# PhotonOnAStick-Wide.net
KiCad netlist of a schematic drawn in EAGLE
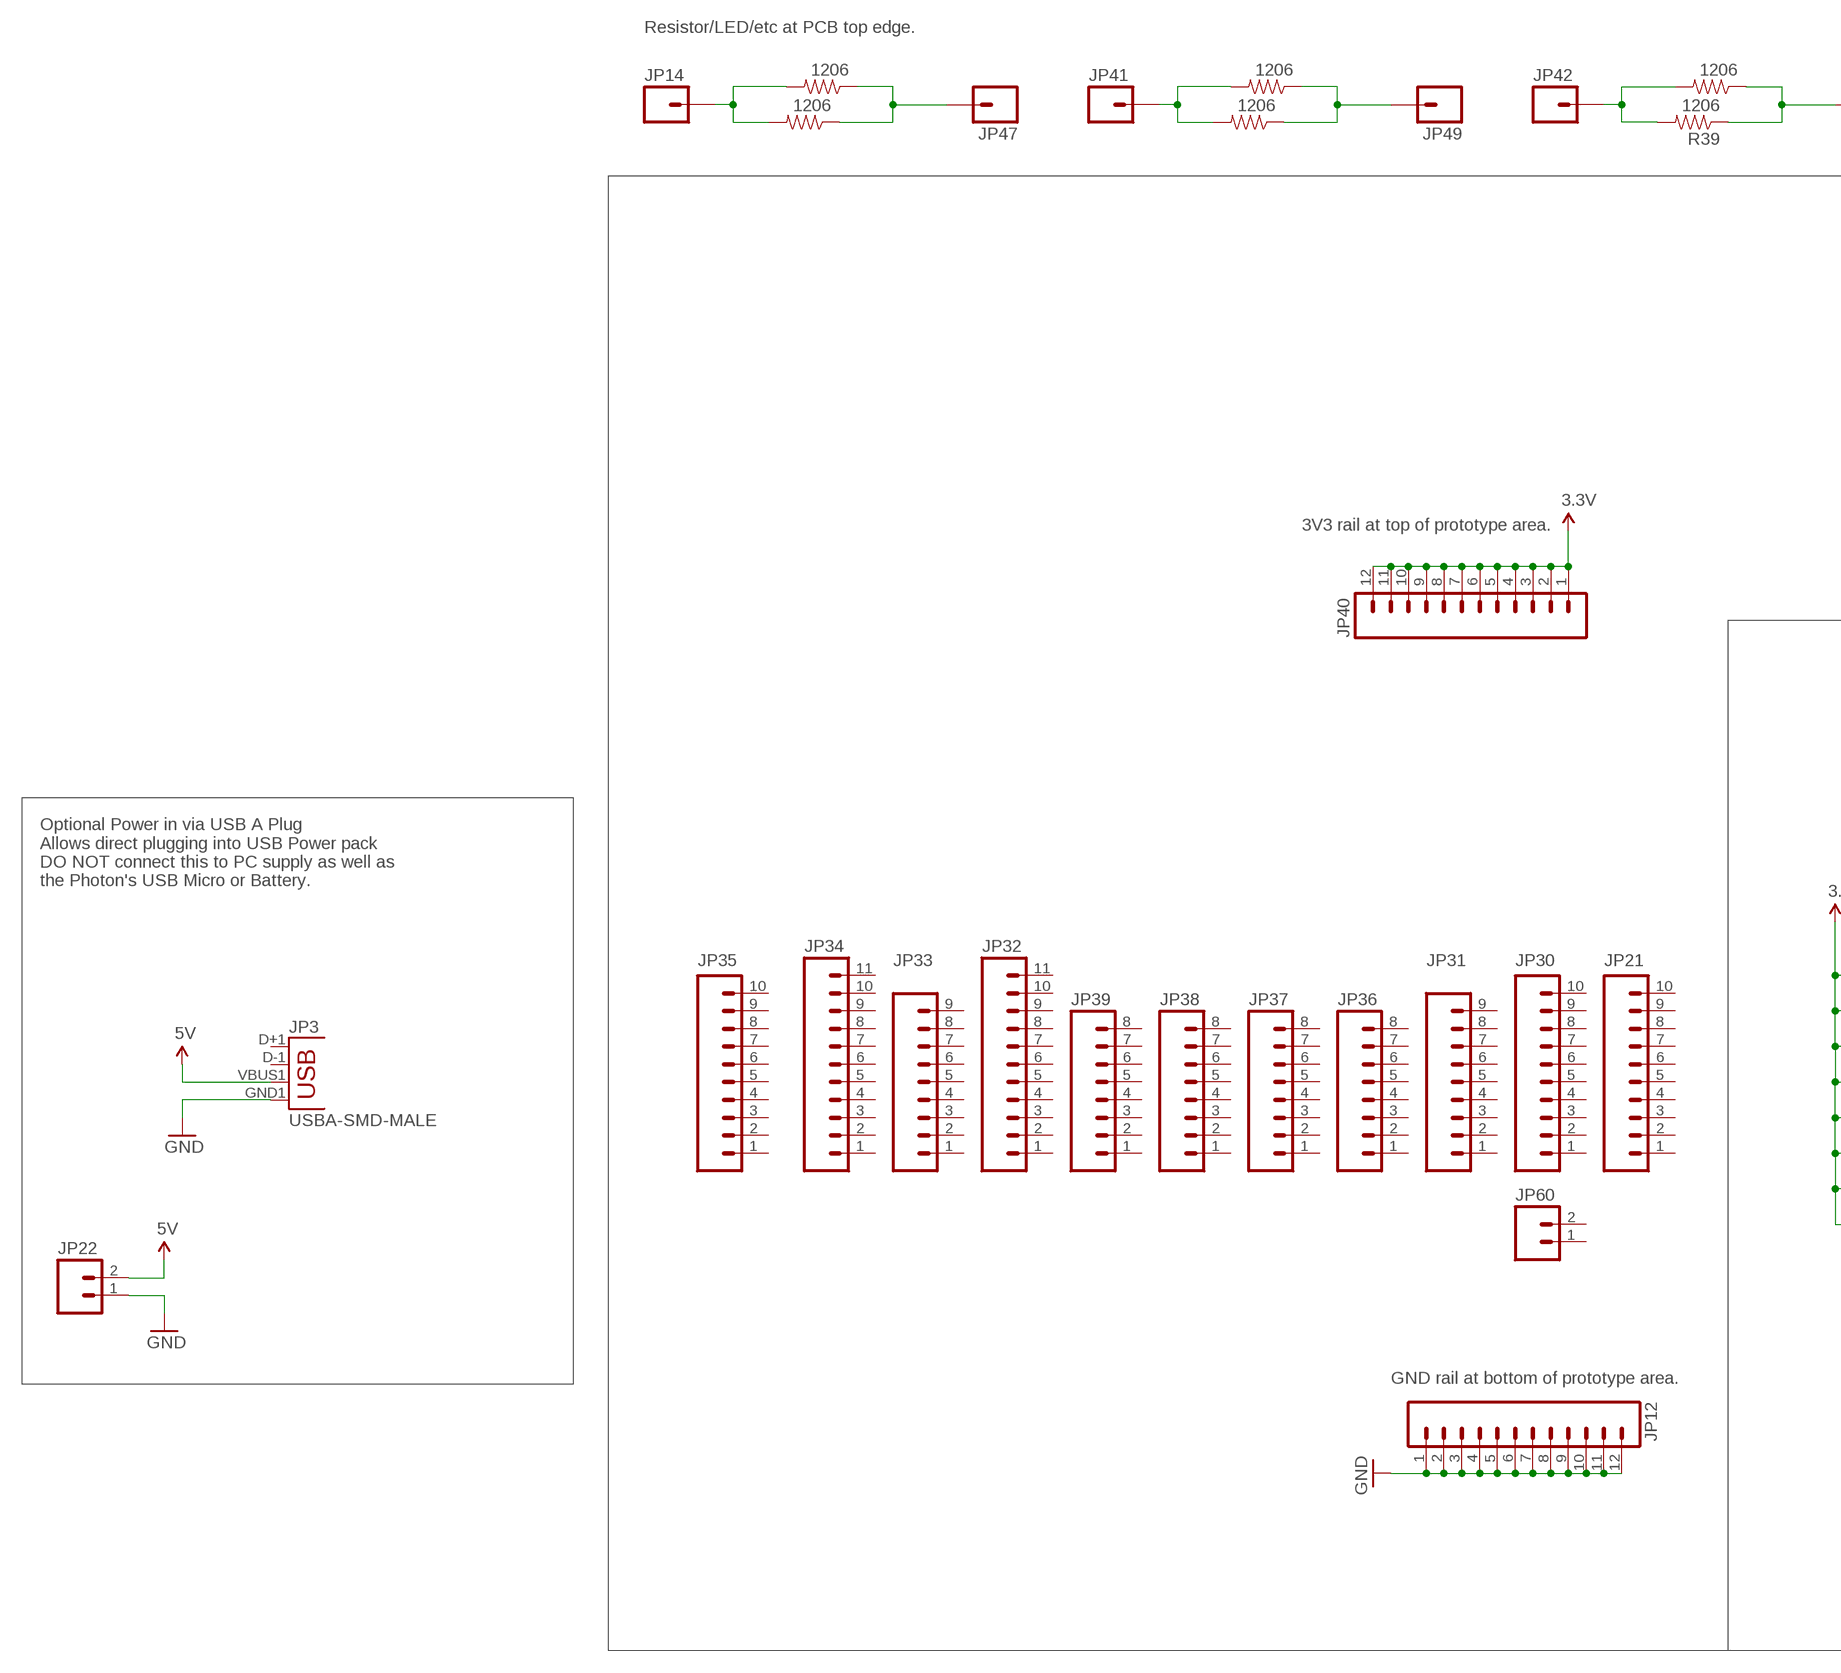
[diagram p0: schematic, sheet 1, part 1 of 2]
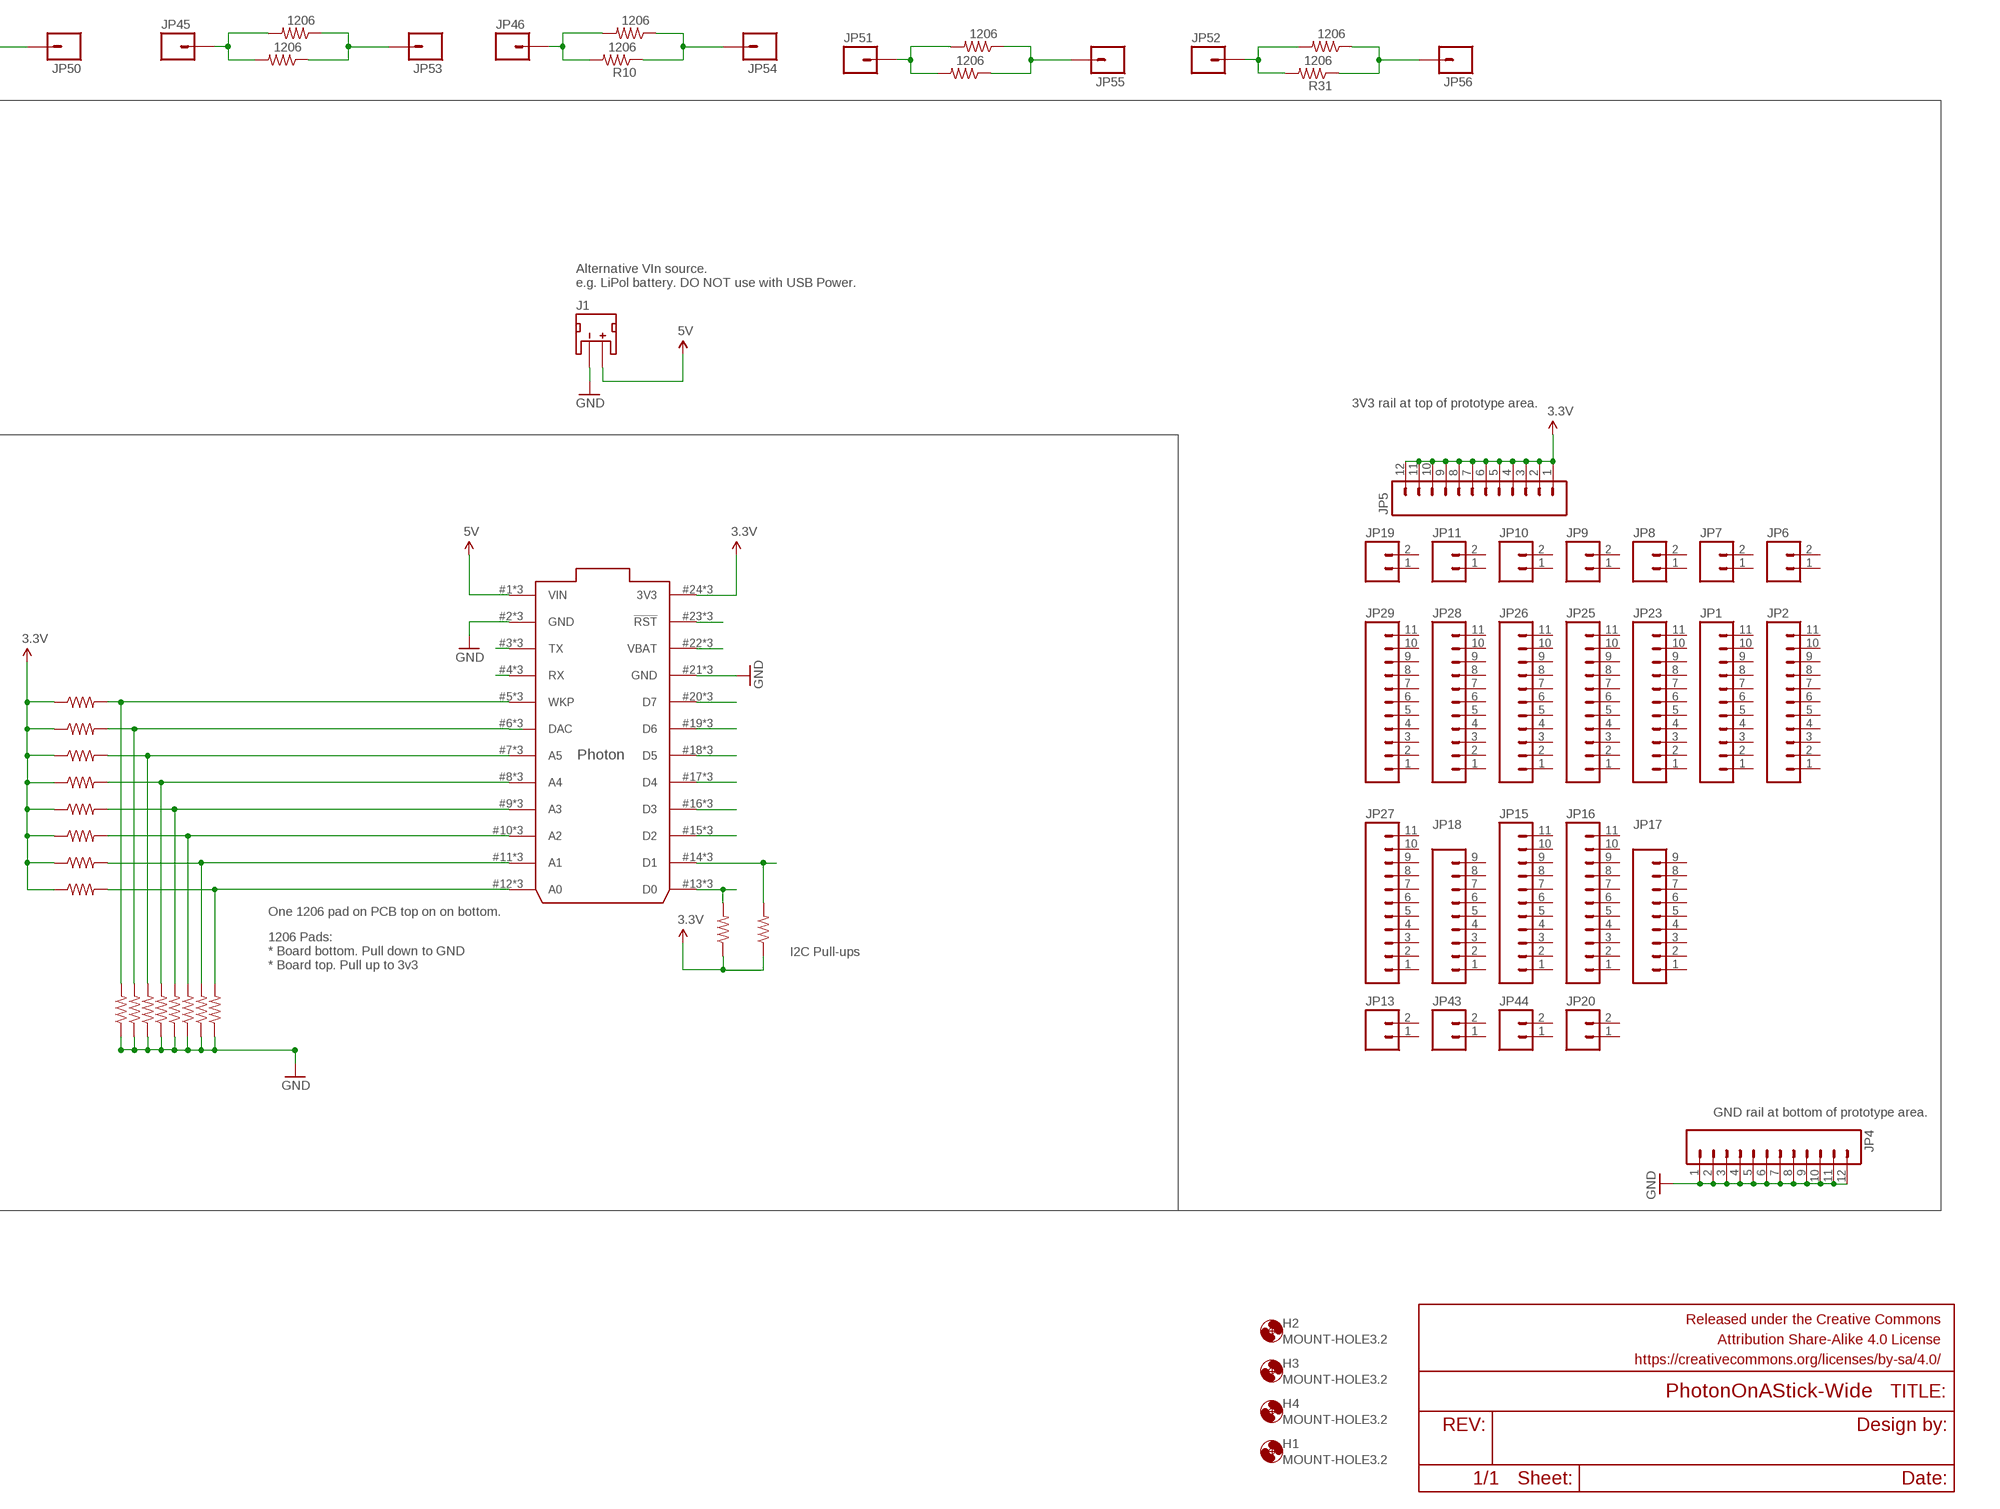
[diagram p1: schematic, sheet 1, part 2 of 2]

(export (version "E")
  (design (tool "Eeschema 10.0.6"))
  (components
    (comp (ref "FRAME1")
      (value "FRAME-LEDGER")
      (footprint "eagle-import:CREATIVE_COMMONS")
      (libsource (lib "eagle-import") (part "FRAME-LEDGER"))
    )
    (comp (ref "H1")
      (value "MOUNT-HOLE3.2")
      (footprint "eagle-import:3,2")
      (libsource (lib "eagle-import") (part "MOUNT-HOLE3.2"))
    )
    (comp (ref "H2")
      (value "MOUNT-HOLE3.2")
      (footprint "eagle-import:3,2")
      (libsource (lib "eagle-import") (part "MOUNT-HOLE3.2"))
    )
    (comp (ref "H3")
      (value "MOUNT-HOLE3.2")
      (footprint "eagle-import:3,2")
      (libsource (lib "eagle-import") (part "MOUNT-HOLE3.2"))
    )
    (comp (ref "H4")
      (value "MOUNT-HOLE3.2")
      (footprint "eagle-import:3,2")
      (libsource (lib "eagle-import") (part "MOUNT-HOLE3.2"))
    )
    (comp (ref "IC1")
      (value "PHOTON_WITH_STACKABLE_HEADERS")
      (footprint "eagle-import:PHOTON_STACKABLE")
      (libsource (lib "eagle-import") (part "PHOTON_WITH_STACKABLE_HEADERS"))
    )
    (comp (ref "J1")
      (value "JST_2MM_MALE")
      (footprint "eagle-import:JST-2-SMD")
      (libsource (lib "eagle-import") (part "JST_2MM_MALE"))
    )
    (comp (ref "JP1")
      (value "M111X11_NO_SILK")
      (footprint "eagle-import:1X11_NO_SILK")
      (libsource (lib "eagle-import") (part "M111X11_NO_SILK"))
    )
    (comp (ref "JP2")
      (value "M111X11_NO_SILK")
      (footprint "eagle-import:1X11_NO_SILK")
      (libsource (lib "eagle-import") (part "M111X11_NO_SILK"))
    )
    (comp (ref "JP3")
      (value "USBA-SMD-MALE")
      (footprint "eagle-import:USB-A-SMT-MALE")
      (libsource (lib "eagle-import") (part "USBA-SMD-MALE"))
    )
    (comp (ref "JP4")
      (value "M12PTH")
      (footprint "eagle-import:1X12")
      (libsource (lib "eagle-import") (part "M12PTH"))
    )
    (comp (ref "JP5")
      (value "M12PTH")
      (footprint "eagle-import:1X12")
      (libsource (lib "eagle-import") (part "M12PTH"))
    )
    (comp (ref "JP6")
      (value "M021X02_NO_SILK")
      (footprint "eagle-import:1X02_NO_SILK")
      (libsource (lib "eagle-import") (part "M021X02_NO_SILK"))
    )
    (comp (ref "JP7")
      (value "M021X02_NO_SILK")
      (footprint "eagle-import:1X02_NO_SILK")
      (libsource (lib "eagle-import") (part "M021X02_NO_SILK"))
    )
    (comp (ref "JP8")
      (value "M021X02_NO_SILK")
      (footprint "eagle-import:1X02_NO_SILK")
      (libsource (lib "eagle-import") (part "M021X02_NO_SILK"))
    )
    (comp (ref "JP9")
      (value "M021X02_NO_SILK")
      (footprint "eagle-import:1X02_NO_SILK")
      (libsource (lib "eagle-import") (part "M021X02_NO_SILK"))
    )
    (comp (ref "JP10")
      (value "M021X02_NO_SILK")
      (footprint "eagle-import:1X02_NO_SILK")
      (libsource (lib "eagle-import") (part "M021X02_NO_SILK"))
    )
    (comp (ref "JP11")
      (value "M021X02_NO_SILK")
      (footprint "eagle-import:1X02_NO_SILK")
      (libsource (lib "eagle-import") (part "M021X02_NO_SILK"))
    )
    (comp (ref "JP12")
      (value "M12PTH")
      (footprint "eagle-import:1X12")
      (libsource (lib "eagle-import") (part "M12PTH"))
    )
    (comp (ref "JP13")
      (value "M021X02_NO_SILK")
      (footprint "eagle-import:1X02_NO_SILK")
      (libsource (lib "eagle-import") (part "M021X02_NO_SILK"))
    )
    (comp (ref "JP14")
      (value "M01PTH")
      (footprint "eagle-import:1X01")
      (libsource (lib "eagle-import") (part "M01PTH"))
    )
    (comp (ref "JP15")
      (value "M111X11_NO_SILK")
      (footprint "eagle-import:1X11_NO_SILK")
      (libsource (lib "eagle-import") (part "M111X11_NO_SILK"))
    )
    (comp (ref "JP16")
      (value "M111X11_NO_SILK")
      (footprint "eagle-import:1X11_NO_SILK")
      (libsource (lib "eagle-import") (part "M111X11_NO_SILK"))
    )
    (comp (ref "JP17")
      (value "M09NO_SILK")
      (footprint "eagle-import:1X09_NO_SILK")
      (libsource (lib "eagle-import") (part "M09NO_SILK"))
    )
    (comp (ref "JP18")
      (value "M09NO_SILK")
      (footprint "eagle-import:1X09_NO_SILK")
      (libsource (lib "eagle-import") (part "M09NO_SILK"))
    )
    (comp (ref "JP19")
      (value "M021X02_NO_SILK")
      (footprint "eagle-import:1X02_NO_SILK")
      (libsource (lib "eagle-import") (part "M021X02_NO_SILK"))
    )
    (comp (ref "JP20")
      (value "M021X02_NO_SILK")
      (footprint "eagle-import:1X02_NO_SILK")
      (libsource (lib "eagle-import") (part "M021X02_NO_SILK"))
    )
    (comp (ref "JP21")
      (value "M10NO_SILK_PTH_FEMALE")
      (footprint "eagle-import:1X10_NO_SILK")
      (libsource (lib "eagle-import") (part "M10NO_SILK_PTH_FEMALE"))
    )
    (comp (ref "JP22")
      (value "M021X02_NO_SILK")
      (footprint "eagle-import:1X02_NO_SILK")
      (libsource (lib "eagle-import") (part "M021X02_NO_SILK"))
    )
    (comp (ref "JP23")
      (value "M111X11_NO_SILK")
      (footprint "eagle-import:1X11_NO_SILK")
      (libsource (lib "eagle-import") (part "M111X11_NO_SILK"))
    )
    (comp (ref "JP25")
      (value "M111X11_NO_SILK")
      (footprint "eagle-import:1X11_NO_SILK")
      (libsource (lib "eagle-import") (part "M111X11_NO_SILK"))
    )
    (comp (ref "JP26")
      (value "M111X11_NO_SILK")
      (footprint "eagle-import:1X11_NO_SILK")
      (libsource (lib "eagle-import") (part "M111X11_NO_SILK"))
    )
    (comp (ref "JP27")
      (value "M111X11_NO_SILK")
      (footprint "eagle-import:1X11_NO_SILK")
      (libsource (lib "eagle-import") (part "M111X11_NO_SILK"))
    )
    (comp (ref "JP28")
      (value "M111X11_NO_SILK")
      (footprint "eagle-import:1X11_NO_SILK")
      (libsource (lib "eagle-import") (part "M111X11_NO_SILK"))
    )
    (comp (ref "JP29")
      (value "M111X11_NO_SILK")
      (footprint "eagle-import:1X11_NO_SILK")
      (libsource (lib "eagle-import") (part "M111X11_NO_SILK"))
    )
    (comp (ref "JP30")
      (value "M10NO_SILK_PTH_FEMALE")
      (footprint "eagle-import:1X10_NO_SILK")
      (libsource (lib "eagle-import") (part "M10NO_SILK_PTH_FEMALE"))
    )
    (comp (ref "JP31")
      (value "M09NO_SILK")
      (footprint "eagle-import:1X09_NO_SILK")
      (libsource (lib "eagle-import") (part "M09NO_SILK"))
    )
    (comp (ref "JP32")
      (value "M111X11_NO_SILK")
      (footprint "eagle-import:1X11_NO_SILK")
      (libsource (lib "eagle-import") (part "M111X11_NO_SILK"))
    )
    (comp (ref "JP33")
      (value "M09NO_SILK")
      (footprint "eagle-import:1X09_NO_SILK")
      (libsource (lib "eagle-import") (part "M09NO_SILK"))
    )
    (comp (ref "JP34")
      (value "M111X11_NO_SILK")
      (footprint "eagle-import:1X11_NO_SILK")
      (libsource (lib "eagle-import") (part "M111X11_NO_SILK"))
    )
    (comp (ref "JP35")
      (value "M10NO_SILK_PTH_FEMALE")
      (footprint "eagle-import:1X10_NO_SILK")
      (libsource (lib "eagle-import") (part "M10NO_SILK_PTH_FEMALE"))
    )
    (comp (ref "JP36")
      (value "M08NO_SILK_FEMALE_PTH")
      (footprint "eagle-import:1X08_NO_SILK")
      (libsource (lib "eagle-import") (part "M08NO_SILK_FEMALE_PTH"))
    )
    (comp (ref "JP37")
      (value "M08NO_SILK_FEMALE_PTH")
      (footprint "eagle-import:1X08_NO_SILK")
      (libsource (lib "eagle-import") (part "M08NO_SILK_FEMALE_PTH"))
    )
    (comp (ref "JP38")
      (value "M08NO_SILK_FEMALE_PTH")
      (footprint "eagle-import:1X08_NO_SILK")
      (libsource (lib "eagle-import") (part "M08NO_SILK_FEMALE_PTH"))
    )
    (comp (ref "JP39")
      (value "M08NO_SILK_FEMALE_PTH")
      (footprint "eagle-import:1X08_NO_SILK")
      (libsource (lib "eagle-import") (part "M08NO_SILK_FEMALE_PTH"))
    )
    (comp (ref "JP40")
      (value "M12PTH")
      (footprint "eagle-import:1X12")
      (libsource (lib "eagle-import") (part "M12PTH"))
    )
    (comp (ref "JP41")
      (value "M01PTH")
      (footprint "eagle-import:1X01")
      (libsource (lib "eagle-import") (part "M01PTH"))
    )
    (comp (ref "JP42")
      (value "M01PTH")
      (footprint "eagle-import:1X01")
      (libsource (lib "eagle-import") (part "M01PTH"))
    )
    (comp (ref "JP43")
      (value "M021X02_NO_SILK")
      (footprint "eagle-import:1X02_NO_SILK")
      (libsource (lib "eagle-import") (part "M021X02_NO_SILK"))
    )
    (comp (ref "JP44")
      (value "M021X02_NO_SILK")
      (footprint "eagle-import:1X02_NO_SILK")
      (libsource (lib "eagle-import") (part "M021X02_NO_SILK"))
    )
    (comp (ref "JP45")
      (value "M01PTH")
      (footprint "eagle-import:1X01")
      (libsource (lib "eagle-import") (part "M01PTH"))
    )
    (comp (ref "JP46")
      (value "M01PTH")
      (footprint "eagle-import:1X01")
      (libsource (lib "eagle-import") (part "M01PTH"))
    )
    (comp (ref "JP47")
      (value "M01PTH")
      (footprint "eagle-import:1X01")
      (libsource (lib "eagle-import") (part "M01PTH"))
    )
    (comp (ref "JP49")
      (value "M01PTH")
      (footprint "eagle-import:1X01")
      (libsource (lib "eagle-import") (part "M01PTH"))
    )
    (comp (ref "JP50")
      (value "M01PTH")
      (footprint "eagle-import:1X01")
      (libsource (lib "eagle-import") (part "M01PTH"))
    )
    (comp (ref "JP51")
      (value "M01PTH")
      (footprint "eagle-import:1X01")
      (libsource (lib "eagle-import") (part "M01PTH"))
    )
    (comp (ref "JP52")
      (value "M01PTH")
      (footprint "eagle-import:1X01")
      (libsource (lib "eagle-import") (part "M01PTH"))
    )
    (comp (ref "JP53")
      (value "M01PTH")
      (footprint "eagle-import:1X01")
      (libsource (lib "eagle-import") (part "M01PTH"))
    )
    (comp (ref "JP54")
      (value "M01PTH")
      (footprint "eagle-import:1X01")
      (libsource (lib "eagle-import") (part "M01PTH"))
    )
    (comp (ref "JP55")
      (value "M01PTH")
      (footprint "eagle-import:1X01")
      (libsource (lib "eagle-import") (part "M01PTH"))
    )
    (comp (ref "JP56")
      (value "M01PTH")
      (footprint "eagle-import:1X01")
      (libsource (lib "eagle-import") (part "M01PTH"))
    )
    (comp (ref "JP60")
      (value "M021X02_NO_SILK")
      (footprint "eagle-import:1X02_NO_SILK")
      (libsource (lib "eagle-import") (part "M021X02_NO_SILK"))
    )
    (comp (ref "R1")
      (value "1206")
      (footprint "eagle-import:1206")
      (libsource (lib "eagle-import") (part "RESISTOR1206"))
    )
    (comp (ref "R2")
      (value "1206")
      (footprint "eagle-import:1206")
      (libsource (lib "eagle-import") (part "RESISTOR1206"))
    )
    (comp (ref "R3")
      (value "1206")
      (footprint "eagle-import:1206")
      (libsource (lib "eagle-import") (part "RESISTOR1206"))
    )
    (comp (ref "R4")
      (value "1206")
      (footprint "eagle-import:1206")
      (libsource (lib "eagle-import") (part "RESISTOR1206"))
    )
    (comp (ref "R5")
      (value "1206")
      (footprint "eagle-import:1206")
      (libsource (lib "eagle-import") (part "RESISTOR1206"))
    )
    (comp (ref "R6")
      (value "1206")
      (footprint "eagle-import:1206")
      (libsource (lib "eagle-import") (part "RESISTOR1206"))
    )
    (comp (ref "R7")
      (value "1206")
      (footprint "eagle-import:1206")
      (libsource (lib "eagle-import") (part "RESISTOR1206"))
    )
    (comp (ref "R8")
      (value "1206")
      (footprint "eagle-import:1206")
      (libsource (lib "eagle-import") (part "RESISTOR1206"))
    )
    (comp (ref "R9")
      (value "1206")
      (footprint "eagle-import:1206")
      (libsource (lib "eagle-import") (part "RESISTOR1206"))
    )
    (comp (ref "R10")
      (value "1206")
      (footprint "eagle-import:1206")
      (libsource (lib "eagle-import") (part "RESISTOR1206"))
    )
    (comp (ref "R12")
      (value "1206")
      (footprint "eagle-import:1206")
      (libsource (lib "eagle-import") (part "RESISTOR1206"))
    )
    (comp (ref "R13")
      (value "1206")
      (footprint "eagle-import:1206")
      (libsource (lib "eagle-import") (part "RESISTOR1206"))
    )
    (comp (ref "R14")
      (value "1206")
      (footprint "eagle-import:1206")
      (libsource (lib "eagle-import") (part "RESISTOR1206"))
    )
    (comp (ref "R15")
      (value "1206")
      (footprint "eagle-import:1206")
      (libsource (lib "eagle-import") (part "RESISTOR1206"))
    )
    (comp (ref "R16")
      (value "1206")
      (footprint "eagle-import:1206")
      (libsource (lib "eagle-import") (part "RESISTOR1206"))
    )
    (comp (ref "R17")
      (value "1206")
      (footprint "eagle-import:1206")
      (libsource (lib "eagle-import") (part "RESISTOR1206"))
    )
    (comp (ref "R19")
      (value "1206")
      (footprint "eagle-import:1206")
      (libsource (lib "eagle-import") (part "RESISTOR1206"))
    )
    (comp (ref "R20")
      (value "1206")
      (footprint "eagle-import:1206")
      (libsource (lib "eagle-import") (part "RESISTOR1206"))
    )
    (comp (ref "R21")
      (value "1206")
      (footprint "eagle-import:1206")
      (libsource (lib "eagle-import") (part "RESISTOR1206"))
    )
    (comp (ref "R22")
      (value "1206")
      (footprint "eagle-import:1206")
      (libsource (lib "eagle-import") (part "RESISTOR1206"))
    )
    (comp (ref "R24")
      (value "1206")
      (footprint "eagle-import:1206")
      (libsource (lib "eagle-import") (part "RESISTOR1206"))
    )
    (comp (ref "R30")
      (value "1206")
      (footprint "eagle-import:1206")
      (libsource (lib "eagle-import") (part "RESISTOR1206"))
    )
    (comp (ref "R31")
      (value "1206")
      (footprint "eagle-import:1206")
      (libsource (lib "eagle-import") (part "RESISTOR1206"))
    )
    (comp (ref "R32")
      (value "1206")
      (footprint "eagle-import:1206")
      (libsource (lib "eagle-import") (part "RESISTOR1206"))
    )
    (comp (ref "R34")
      (value "1206")
      (footprint "eagle-import:1206")
      (libsource (lib "eagle-import") (part "RESISTOR1206"))
    )
    (comp (ref "R35")
      (value "1206")
      (footprint "eagle-import:1206")
      (libsource (lib "eagle-import") (part "RESISTOR1206"))
    )
    (comp (ref "R36")
      (value "1206")
      (footprint "eagle-import:1206")
      (libsource (lib "eagle-import") (part "RESISTOR1206"))
    )
    (comp (ref "R37")
      (value "1206")
      (footprint "eagle-import:1206")
      (libsource (lib "eagle-import") (part "RESISTOR1206"))
    )
    (comp (ref "R39")
      (value "1206")
      (footprint "eagle-import:1206")
      (libsource (lib "eagle-import") (part "RESISTOR1206"))
    )
    (comp (ref "R40")
      (value "1206")
      (footprint "eagle-import:1206")
      (libsource (lib "eagle-import") (part "RESISTOR1206"))
    )
    (comp (ref "R41")
      (value "1206")
      (footprint "eagle-import:1206")
      (libsource (lib "eagle-import") (part "RESISTOR1206"))
    )
    (comp (ref "R44")
      (value "1206")
      (footprint "eagle-import:1206")
      (libsource (lib "eagle-import") (part "RESISTOR1206"))
    )
  )
  (nets
    (net (code "1") (name "3.3V") (class "Default")
      (node (ref "IC1") (pin "#24") (pinfunction "3V3_#24") (pintype "power_in"))
      (node (ref "IC1") (pin "24") (pinfunction "3V3_24") (pintype "power_in"))
      (node (ref "IC1") (pin "@24") (pinfunction "3V3_@24") (pintype "power_in"))
      (node (ref "JP40") (pin "1") (pinfunction "1_1") (pintype "passive"))
      (node (ref "JP40") (pin "10") (pinfunction "10_10") (pintype "passive"))
      (node (ref "JP40") (pin "11") (pinfunction "11_11") (pintype "passive"))
      (node (ref "JP40") (pin "12") (pinfunction "12_12") (pintype "passive"))
      (node (ref "JP40") (pin "2") (pinfunction "2_2") (pintype "passive"))
      (node (ref "JP40") (pin "3") (pinfunction "3_3") (pintype "passive"))
      (node (ref "JP40") (pin "4") (pinfunction "4_4") (pintype "passive"))
      (node (ref "JP40") (pin "5") (pinfunction "5_5") (pintype "passive"))
      (node (ref "JP40") (pin "6") (pinfunction "6_6") (pintype "passive"))
      (node (ref "JP40") (pin "7") (pinfunction "7_7") (pintype "passive"))
      (node (ref "JP40") (pin "8") (pinfunction "8_8") (pintype "passive"))
      (node (ref "JP40") (pin "9") (pinfunction "9_9") (pintype "passive"))
      (node (ref "JP5") (pin "1") (pinfunction "1_1") (pintype "passive"))
      (node (ref "JP5") (pin "10") (pinfunction "10_10") (pintype "passive"))
      (node (ref "JP5") (pin "11") (pinfunction "11_11") (pintype "passive"))
      (node (ref "JP5") (pin "12") (pinfunction "12_12") (pintype "passive"))
      (node (ref "JP5") (pin "2") (pinfunction "2_2") (pintype "passive"))
      (node (ref "JP5") (pin "3") (pinfunction "3_3") (pintype "passive"))
      (node (ref "JP5") (pin "4") (pinfunction "4_4") (pintype "passive"))
      (node (ref "JP5") (pin "5") (pinfunction "5_5") (pintype "passive"))
      (node (ref "JP5") (pin "6") (pinfunction "6_6") (pintype "passive"))
      (node (ref "JP5") (pin "7") (pinfunction "7_7") (pintype "passive"))
      (node (ref "JP5") (pin "8") (pinfunction "8_8") (pintype "passive"))
      (node (ref "JP5") (pin "9") (pinfunction "9_9") (pintype "passive"))
      (node (ref "R1") (pin "1") (pinfunction "1_1") (pintype "passive"))
      (node (ref "R12") (pin "1") (pinfunction "1_1") (pintype "passive"))
      (node (ref "R15") (pin "1") (pinfunction "1_1") (pintype "passive"))
      (node (ref "R2") (pin "1") (pinfunction "1_1") (pintype "passive"))
      (node (ref "R3") (pin "1") (pinfunction "1_1") (pintype "passive"))
      (node (ref "R4") (pin "1") (pinfunction "1_1") (pintype "passive"))
      (node (ref "R5") (pin "1") (pinfunction "1_1") (pintype "passive"))
      (node (ref "R6") (pin "1") (pinfunction "1_1") (pintype "passive"))
      (node (ref "R7") (pin "1") (pinfunction "1_1") (pintype "passive"))
      (node (ref "R9") (pin "1") (pinfunction "1_1") (pintype "passive"))
    )
    (net (code "2") (name "5V") (class "Default")
      (node (ref "IC1") (pin "#1") (pinfunction "VIN_#1") (pintype "power_in"))
      (node (ref "IC1") (pin "1") (pinfunction "VIN_1") (pintype "power_in"))
      (node (ref "IC1") (pin "@1") (pinfunction "VIN_@1") (pintype "power_in"))
      (node (ref "J1") (pin "2") (pinfunction "+_2") (pintype "bidirectional"))
      (node (ref "JP22") (pin "2") (pinfunction "2_2") (pintype "passive"))
      (node (ref "JP3") (pin "VBUS1") (pinfunction "VBUS_VBUS1") (pintype "bidirectional"))
    )
    (net (code "3") (name "GND") (class "Default")
      (node (ref "IC1") (pin "#2") (pinfunction "GND_#2") (pintype "power_in"))
      (node (ref "IC1") (pin "#21") (pinfunction "GND_#21") (pintype "power_in"))
      (node (ref "IC1") (pin "2") (pinfunction "GND_2") (pintype "power_in"))
      (node (ref "IC1") (pin "21") (pinfunction "GND_21") (pintype "power_in"))
      (node (ref "IC1") (pin "@2") (pinfunction "GND_@2") (pintype "power_in"))
      (node (ref "IC1") (pin "@21") (pinfunction "GND_@21") (pintype "power_in"))
      (node (ref "J1") (pin "1") (pinfunction "-_1") (pintype "bidirectional"))
      (node (ref "JP12") (pin "1") (pinfunction "1_1") (pintype "passive"))
      (node (ref "JP12") (pin "10") (pinfunction "10_10") (pintype "passive"))
      (node (ref "JP12") (pin "11") (pinfunction "11_11") (pintype "passive"))
      (node (ref "JP12") (pin "12") (pinfunction "12_12") (pintype "passive"))
      (node (ref "JP12") (pin "2") (pinfunction "2_2") (pintype "passive"))
      (node (ref "JP12") (pin "3") (pinfunction "3_3") (pintype "passive"))
      (node (ref "JP12") (pin "4") (pinfunction "4_4") (pintype "passive"))
      (node (ref "JP12") (pin "5") (pinfunction "5_5") (pintype "passive"))
      (node (ref "JP12") (pin "6") (pinfunction "6_6") (pintype "passive"))
      (node (ref "JP12") (pin "7") (pinfunction "7_7") (pintype "passive"))
      (node (ref "JP12") (pin "8") (pinfunction "8_8") (pintype "passive"))
      (node (ref "JP12") (pin "9") (pinfunction "9_9") (pintype "passive"))
      (node (ref "JP22") (pin "1") (pinfunction "1_1") (pintype "passive"))
      (node (ref "JP3") (pin "GND1") (pinfunction "GND_GND1") (pintype "bidirectional"))
      (node (ref "JP4") (pin "1") (pinfunction "1_1") (pintype "passive"))
      (node (ref "JP4") (pin "10") (pinfunction "10_10") (pintype "passive"))
      (node (ref "JP4") (pin "11") (pinfunction "11_11") (pintype "passive"))
      (node (ref "JP4") (pin "12") (pinfunction "12_12") (pintype "passive"))
      (node (ref "JP4") (pin "2") (pinfunction "2_2") (pintype "passive"))
      (node (ref "JP4") (pin "3") (pinfunction "3_3") (pintype "passive"))
      (node (ref "JP4") (pin "4") (pinfunction "4_4") (pintype "passive"))
      (node (ref "JP4") (pin "5") (pinfunction "5_5") (pintype "passive"))
      (node (ref "JP4") (pin "6") (pinfunction "6_6") (pintype "passive"))
      (node (ref "JP4") (pin "7") (pinfunction "7_7") (pintype "passive"))
      (node (ref "JP4") (pin "8") (pinfunction "8_8") (pintype "passive"))
      (node (ref "JP4") (pin "9") (pinfunction "9_9") (pintype "passive"))
      (node (ref "R13") (pin "1") (pinfunction "1_1") (pintype "passive"))
      (node (ref "R14") (pin "1") (pinfunction "1_1") (pintype "passive"))
      (node (ref "R16") (pin "1") (pinfunction "1_1") (pintype "passive"))
      (node (ref "R19") (pin "1") (pinfunction "1_1") (pintype "passive"))
      (node (ref "R20") (pin "1") (pinfunction "1_1") (pintype "passive"))
      (node (ref "R21") (pin "1") (pinfunction "1_1") (pintype "passive"))
      (node (ref "R22") (pin "1") (pinfunction "1_1") (pintype "passive"))
      (node (ref "R8") (pin "1") (pinfunction "1_1") (pintype "passive"))
    )
    (net (code "4") (name "Net-(IC1-A0-Pad#12)") (class "Default")
      (node (ref "IC1") (pin "#12") (pinfunction "A0_#12") (pintype "bidirectional"))
      (node (ref "IC1") (pin "12") (pinfunction "A0_12") (pintype "bidirectional"))
      (node (ref "IC1") (pin "@12") (pinfunction "A0_@12") (pintype "bidirectional"))
      (node (ref "R22") (pin "2") (pinfunction "2_2") (pintype "passive"))
      (node (ref "R7") (pin "2") (pinfunction "2_2") (pintype "passive"))
    )
    (net (code "5") (name "Net-(IC1-A1-Pad#11)") (class "Default")
      (node (ref "IC1") (pin "#11") (pinfunction "A1_#11") (pintype "bidirectional"))
      (node (ref "IC1") (pin "11") (pinfunction "A1_11") (pintype "bidirectional"))
      (node (ref "IC1") (pin "@11") (pinfunction "A1_@11") (pintype "bidirectional"))
      (node (ref "R21") (pin "2") (pinfunction "2_2") (pintype "passive"))
      (node (ref "R6") (pin "2") (pinfunction "2_2") (pintype "passive"))
    )
    (net (code "6") (name "Net-(IC1-A2-Pad#10)") (class "Default")
      (node (ref "IC1") (pin "#10") (pinfunction "A2_#10") (pintype "bidirectional"))
      (node (ref "IC1") (pin "10") (pinfunction "A2_10") (pintype "bidirectional"))
      (node (ref "IC1") (pin "@10") (pinfunction "A2_@10") (pintype "bidirectional"))
      (node (ref "R20") (pin "2") (pinfunction "2_2") (pintype "passive"))
      (node (ref "R4") (pin "2") (pinfunction "2_2") (pintype "passive"))
    )
    (net (code "7") (name "Net-(IC1-A3-Pad#9)") (class "Default")
      (node (ref "IC1") (pin "#9") (pinfunction "A3_#9") (pintype "bidirectional"))
      (node (ref "IC1") (pin "9") (pinfunction "A3_9") (pintype "bidirectional"))
      (node (ref "IC1") (pin "@9") (pinfunction "A3_@9") (pintype "bidirectional"))
      (node (ref "R19") (pin "2") (pinfunction "2_2") (pintype "passive"))
      (node (ref "R3") (pin "2") (pinfunction "2_2") (pintype "passive"))
    )
    (net (code "8") (name "Net-(IC1-A4-Pad#8)") (class "Default")
      (node (ref "IC1") (pin "#8") (pinfunction "A4_#8") (pintype "bidirectional"))
      (node (ref "IC1") (pin "8") (pinfunction "A4_8") (pintype "bidirectional"))
      (node (ref "IC1") (pin "@8") (pinfunction "A4_@8") (pintype "bidirectional"))
      (node (ref "R14") (pin "2") (pinfunction "2_2") (pintype "passive"))
      (node (ref "R2") (pin "2") (pinfunction "2_2") (pintype "passive"))
    )
    (net (code "9") (name "Net-(IC1-A5-Pad#7)") (class "Default")
      (node (ref "IC1") (pin "#7") (pinfunction "A5_#7") (pintype "bidirectional"))
      (node (ref "IC1") (pin "7") (pinfunction "A5_7") (pintype "bidirectional"))
      (node (ref "IC1") (pin "@7") (pinfunction "A5_@7") (pintype "bidirectional"))
      (node (ref "R1") (pin "2") (pinfunction "2_2") (pintype "passive"))
      (node (ref "R13") (pin "2") (pinfunction "2_2") (pintype "passive"))
    )
    (net (code "10") (name "Net-(IC1-D0-Pad#13)") (class "Default")
      (node (ref "IC1") (pin "#13") (pinfunction "D0_#13") (pintype "bidirectional"))
      (node (ref "IC1") (pin "13") (pinfunction "D0_13") (pintype "bidirectional"))
      (node (ref "IC1") (pin "@13") (pinfunction "D0_@13") (pintype "bidirectional"))
      (node (ref "R5") (pin "2") (pinfunction "2_2") (pintype "passive"))
    )
    (net (code "11") (name "Net-(IC1-D1-Pad#14)") (class "Default")
      (node (ref "IC1") (pin "#14") (pinfunction "D1_#14") (pintype "bidirectional"))
      (node (ref "IC1") (pin "14") (pinfunction "D1_14") (pintype "bidirectional"))
      (node (ref "IC1") (pin "@14") (pinfunction "D1_@14") (pintype "bidirectional"))
      (node (ref "R9") (pin "2") (pinfunction "2_2") (pintype "passive"))
    )
    (net (code "12") (name "Net-(IC1-D2-Pad#15)") (class "Default")
      (node (ref "IC1") (pin "#15") (pinfunction "D2_#15") (pintype "bidirectional"))
      (node (ref "IC1") (pin "15") (pinfunction "D2_15") (pintype "bidirectional"))
      (node (ref "IC1") (pin "@15") (pinfunction "D2_@15") (pintype "bidirectional"))
    )
    (net (code "13") (name "Net-(IC1-D3-Pad#16)") (class "Default")
      (node (ref "IC1") (pin "#16") (pinfunction "D3_#16") (pintype "bidirectional"))
      (node (ref "IC1") (pin "16") (pinfunction "D3_16") (pintype "bidirectional"))
      (node (ref "IC1") (pin "@16") (pinfunction "D3_@16") (pintype "bidirectional"))
    )
    (net (code "14") (name "Net-(IC1-D4-Pad#17)") (class "Default")
      (node (ref "IC1") (pin "#17") (pinfunction "D4_#17") (pintype "bidirectional"))
      (node (ref "IC1") (pin "17") (pinfunction "D4_17") (pintype "bidirectional"))
      (node (ref "IC1") (pin "@17") (pinfunction "D4_@17") (pintype "bidirectional"))
    )
    (net (code "15") (name "Net-(IC1-D5-Pad#18)") (class "Default")
      (node (ref "IC1") (pin "#18") (pinfunction "D5_#18") (pintype "bidirectional"))
      (node (ref "IC1") (pin "18") (pinfunction "D5_18") (pintype "bidirectional"))
      (node (ref "IC1") (pin "@18") (pinfunction "D5_@18") (pintype "bidirectional"))
    )
    (net (code "16") (name "Net-(IC1-D6-Pad#19)") (class "Default")
      (node (ref "IC1") (pin "#19") (pinfunction "D6_#19") (pintype "bidirectional"))
      (node (ref "IC1") (pin "19") (pinfunction "D6_19") (pintype "bidirectional"))
      (node (ref "IC1") (pin "@19") (pinfunction "D6_@19") (pintype "bidirectional"))
    )
    (net (code "17") (name "Net-(IC1-D7-Pad#20)") (class "Default")
      (node (ref "IC1") (pin "#20") (pinfunction "D7_#20") (pintype "bidirectional"))
      (node (ref "IC1") (pin "20") (pinfunction "D7_20") (pintype "bidirectional"))
      (node (ref "IC1") (pin "@20") (pinfunction "D7_@20") (pintype "bidirectional"))
    )
    (net (code "18") (name "Net-(IC1-DAC-Pad#6)") (class "Default")
      (node (ref "IC1") (pin "#6") (pinfunction "DAC_#6") (pintype "bidirectional"))
      (node (ref "IC1") (pin "6") (pinfunction "DAC_6") (pintype "bidirectional"))
      (node (ref "IC1") (pin "@6") (pinfunction "DAC_@6") (pintype "bidirectional"))
      (node (ref "R15") (pin "2") (pinfunction "2_2") (pintype "passive"))
      (node (ref "R16") (pin "2") (pinfunction "2_2") (pintype "passive"))
    )
    (net (code "19") (name "Net-(IC1-RX-Pad#4)") (class "Default")
      (node (ref "IC1") (pin "#4") (pinfunction "RX_#4") (pintype "bidirectional"))
      (node (ref "IC1") (pin "4") (pinfunction "RX_4") (pintype "bidirectional"))
      (node (ref "IC1") (pin "@4") (pinfunction "RX_@4") (pintype "bidirectional"))
    )
    (net (code "20") (name "Net-(IC1-TX-Pad#3)") (class "Default")
      (node (ref "IC1") (pin "#3") (pinfunction "TX_#3") (pintype "bidirectional"))
      (node (ref "IC1") (pin "3") (pinfunction "TX_3") (pintype "bidirectional"))
      (node (ref "IC1") (pin "@3") (pinfunction "TX_@3") (pintype "bidirectional"))
    )
    (net (code "21") (name "Net-(IC1-VBAT-Pad#22)") (class "Default")
      (node (ref "IC1") (pin "#22") (pinfunction "VBAT_#22") (pintype "power_in"))
      (node (ref "IC1") (pin "22") (pinfunction "VBAT_22") (pintype "power_in"))
      (node (ref "IC1") (pin "@22") (pinfunction "VBAT_@22") (pintype "power_in"))
    )
    (net (code "22") (name "Net-(IC1-WKP-Pad#5)") (class "Default")
      (node (ref "IC1") (pin "#5") (pinfunction "WKP_#5") (pintype "bidirectional"))
      (node (ref "IC1") (pin "5") (pinfunction "WKP_5") (pintype "bidirectional"))
      (node (ref "IC1") (pin "@5") (pinfunction "WKP_@5") (pintype "bidirectional"))
      (node (ref "R12") (pin "2") (pinfunction "2_2") (pintype "passive"))
      (node (ref "R8") (pin "2") (pinfunction "2_2") (pintype "passive"))
    )
    (net (code "23") (name "Net-(IC1-~{RST}-Pad#23)") (class "Default")
      (node (ref "IC1") (pin "#23") (pinfunction "~{RST}_#23") (pintype "bidirectional"))
      (node (ref "IC1") (pin "23") (pinfunction "~{RST}_23") (pintype "bidirectional"))
      (node (ref "IC1") (pin "@23") (pinfunction "~{RST}_@23") (pintype "bidirectional"))
    )
    (net (code "24") (name "Net-(JP14-Pad1)") (class "Default")
      (node (ref "JP14") (pin "1") (pinfunction "1_1") (pintype "passive"))
      (node (ref "R34") (pin "2") (pinfunction "2_2") (pintype "passive"))
      (node (ref "R35") (pin "2") (pinfunction "2_2") (pintype "passive"))
    )
    (net (code "25") (name "Net-(JP41-Pad1)") (class "Default")
      (node (ref "JP41") (pin "1") (pinfunction "1_1") (pintype "passive"))
      (node (ref "R40") (pin "2") (pinfunction "2_2") (pintype "passive"))
      (node (ref "R41") (pin "2") (pinfunction "2_2") (pintype "passive"))
    )
    (net (code "26") (name "Net-(JP42-Pad1)") (class "Default")
      (node (ref "JP42") (pin "1") (pinfunction "1_1") (pintype "passive"))
      (node (ref "R39") (pin "2") (pinfunction "2_2") (pintype "passive"))
      (node (ref "R44") (pin "2") (pinfunction "2_2") (pintype "passive"))
    )
    (net (code "27") (name "Net-(JP45-Pad1)") (class "Default")
      (node (ref "JP45") (pin "1") (pinfunction "1_1") (pintype "passive"))
      (node (ref "R17") (pin "2") (pinfunction "2_2") (pintype "passive"))
      (node (ref "R24") (pin "2") (pinfunction "2_2") (pintype "passive"))
    )
    (net (code "28") (name "Net-(JP46-Pad1)") (class "Default")
      (node (ref "JP46") (pin "1") (pinfunction "1_1") (pintype "passive"))
      (node (ref "R10") (pin "2") (pinfunction "2_2") (pintype "passive"))
      (node (ref "R30") (pin "2") (pinfunction "2_2") (pintype "passive"))
    )
    (net (code "29") (name "Net-(JP47-Pad1)") (class "Default")
      (node (ref "JP47") (pin "1") (pinfunction "1_1") (pintype "passive"))
      (node (ref "R34") (pin "1") (pinfunction "1_1") (pintype "passive"))
      (node (ref "R35") (pin "1") (pinfunction "1_1") (pintype "passive"))
    )
    (net (code "30") (name "Net-(JP49-Pad1)") (class "Default")
      (node (ref "JP49") (pin "1") (pinfunction "1_1") (pintype "passive"))
      (node (ref "R40") (pin "1") (pinfunction "1_1") (pintype "passive"))
      (node (ref "R41") (pin "1") (pinfunction "1_1") (pintype "passive"))
    )
    (net (code "31") (name "Net-(JP50-Pad1)") (class "Default")
      (node (ref "JP50") (pin "1") (pinfunction "1_1") (pintype "passive"))
      (node (ref "R39") (pin "1") (pinfunction "1_1") (pintype "passive"))
      (node (ref "R44") (pin "1") (pinfunction "1_1") (pintype "passive"))
    )
    (net (code "32") (name "Net-(JP51-Pad1)") (class "Default")
      (node (ref "JP51") (pin "1") (pinfunction "1_1") (pintype "passive"))
      (node (ref "R32") (pin "2") (pinfunction "2_2") (pintype "passive"))
      (node (ref "R36") (pin "2") (pinfunction "2_2") (pintype "passive"))
    )
    (net (code "33") (name "Net-(JP52-Pad1)") (class "Default")
      (node (ref "JP52") (pin "1") (pinfunction "1_1") (pintype "passive"))
      (node (ref "R31") (pin "2") (pinfunction "2_2") (pintype "passive"))
      (node (ref "R37") (pin "2") (pinfunction "2_2") (pintype "passive"))
    )
    (net (code "34") (name "Net-(JP53-Pad1)") (class "Default")
      (node (ref "JP53") (pin "1") (pinfunction "1_1") (pintype "passive"))
      (node (ref "R17") (pin "1") (pinfunction "1_1") (pintype "passive"))
      (node (ref "R24") (pin "1") (pinfunction "1_1") (pintype "passive"))
    )
    (net (code "35") (name "Net-(JP54-Pad1)") (class "Default")
      (node (ref "JP54") (pin "1") (pinfunction "1_1") (pintype "passive"))
      (node (ref "R10") (pin "1") (pinfunction "1_1") (pintype "passive"))
      (node (ref "R30") (pin "1") (pinfunction "1_1") (pintype "passive"))
    )
    (net (code "36") (name "Net-(JP55-Pad1)") (class "Default")
      (node (ref "JP55") (pin "1") (pinfunction "1_1") (pintype "passive"))
      (node (ref "R32") (pin "1") (pinfunction "1_1") (pintype "passive"))
      (node (ref "R36") (pin "1") (pinfunction "1_1") (pintype "passive"))
    )
    (net (code "37") (name "Net-(JP56-Pad1)") (class "Default")
      (node (ref "JP56") (pin "1") (pinfunction "1_1") (pintype "passive"))
      (node (ref "R31") (pin "1") (pinfunction "1_1") (pintype "passive"))
      (node (ref "R37") (pin "1") (pinfunction "1_1") (pintype "passive"))
    )
    (net (code "38") (name "unconnected-(J1-PAD1-PadNC1)") (class "Default")
      (node (ref "J1") (pin "NC1") (pinfunction "PAD1_NC1") (pintype "bidirectional"))
    )
    (net (code "39") (name "unconnected-(J1-PAD2-PadNC2)") (class "Default")
      (node (ref "J1") (pin "NC2") (pinfunction "PAD2_NC2") (pintype "bidirectional"))
    )
    (net (code "40") (name "unconnected-(JP1-Pad1)") (class "Default")
      (node (ref "JP1") (pin "1") (pinfunction "1_1") (pintype "passive"))
    )
    (net (code "41") (name "unconnected-(JP1-Pad2)") (class "Default")
      (node (ref "JP1") (pin "2") (pinfunction "2_2") (pintype "passive"))
    )
    (net (code "42") (name "unconnected-(JP1-Pad3)") (class "Default")
      (node (ref "JP1") (pin "3") (pinfunction "3_3") (pintype "passive"))
    )
    (net (code "43") (name "unconnected-(JP1-Pad4)") (class "Default")
      (node (ref "JP1") (pin "4") (pinfunction "4_4") (pintype "passive"))
    )
    (net (code "44") (name "unconnected-(JP1-Pad5)") (class "Default")
      (node (ref "JP1") (pin "5") (pinfunction "5_5") (pintype "passive"))
    )
    (net (code "45") (name "unconnected-(JP1-Pad6)") (class "Default")
      (node (ref "JP1") (pin "6") (pinfunction "6_6") (pintype "passive"))
    )
    (net (code "46") (name "unconnected-(JP1-Pad7)") (class "Default")
      (node (ref "JP1") (pin "7") (pinfunction "7_7") (pintype "passive"))
    )
    (net (code "47") (name "unconnected-(JP1-Pad8)") (class "Default")
      (node (ref "JP1") (pin "8") (pinfunction "8_8") (pintype "passive"))
    )
    (net (code "48") (name "unconnected-(JP1-Pad9)") (class "Default")
      (node (ref "JP1") (pin "9") (pinfunction "9_9") (pintype "passive"))
    )
    (net (code "49") (name "unconnected-(JP1-Pad10)") (class "Default")
      (node (ref "JP1") (pin "10") (pinfunction "10_10") (pintype "passive"))
    )
    (net (code "50") (name "unconnected-(JP1-Pad11)") (class "Default")
      (node (ref "JP1") (pin "11") (pinfunction "11_11") (pintype "passive"))
    )
    (net (code "51") (name "unconnected-(JP2-Pad1)") (class "Default")
      (node (ref "JP2") (pin "1") (pinfunction "1_1") (pintype "passive"))
    )
    (net (code "52") (name "unconnected-(JP2-Pad2)") (class "Default")
      (node (ref "JP2") (pin "2") (pinfunction "2_2") (pintype "passive"))
    )
    (net (code "53") (name "unconnected-(JP2-Pad3)") (class "Default")
      (node (ref "JP2") (pin "3") (pinfunction "3_3") (pintype "passive"))
    )
    (net (code "54") (name "unconnected-(JP2-Pad4)") (class "Default")
      (node (ref "JP2") (pin "4") (pinfunction "4_4") (pintype "passive"))
    )
    (net (code "55") (name "unconnected-(JP2-Pad5)") (class "Default")
      (node (ref "JP2") (pin "5") (pinfunction "5_5") (pintype "passive"))
    )
    (net (code "56") (name "unconnected-(JP2-Pad6)") (class "Default")
      (node (ref "JP2") (pin "6") (pinfunction "6_6") (pintype "passive"))
    )
    (net (code "57") (name "unconnected-(JP2-Pad7)") (class "Default")
      (node (ref "JP2") (pin "7") (pinfunction "7_7") (pintype "passive"))
    )
    (net (code "58") (name "unconnected-(JP2-Pad8)") (class "Default")
      (node (ref "JP2") (pin "8") (pinfunction "8_8") (pintype "passive"))
    )
    (net (code "59") (name "unconnected-(JP2-Pad9)") (class "Default")
      (node (ref "JP2") (pin "9") (pinfunction "9_9") (pintype "passive"))
    )
    (net (code "60") (name "unconnected-(JP2-Pad10)") (class "Default")
      (node (ref "JP2") (pin "10") (pinfunction "10_10") (pintype "passive"))
    )
    (net (code "61") (name "unconnected-(JP2-Pad11)") (class "Default")
      (node (ref "JP2") (pin "11") (pinfunction "11_11") (pintype "passive"))
    )
    (net (code "62") (name "unconnected-(JP3-D+-PadD+1)") (class "Default")
      (node (ref "JP3") (pin "D+1") (pinfunction "D+_D+1") (pintype "bidirectional"))
    )
    (net (code "63") (name "unconnected-(JP3-D--PadD-1)") (class "Default")
      (node (ref "JP3") (pin "D-1") (pinfunction "D-_D-1") (pintype "bidirectional"))
    )
    (net (code "64") (name "unconnected-(JP6-Pad1)") (class "Default")
      (node (ref "JP6") (pin "1") (pinfunction "1_1") (pintype "passive"))
    )
    (net (code "65") (name "unconnected-(JP6-Pad2)") (class "Default")
      (node (ref "JP6") (pin "2") (pinfunction "2_2") (pintype "passive"))
    )
    (net (code "66") (name "unconnected-(JP7-Pad1)") (class "Default")
      (node (ref "JP7") (pin "1") (pinfunction "1_1") (pintype "passive"))
    )
    (net (code "67") (name "unconnected-(JP7-Pad2)") (class "Default")
      (node (ref "JP7") (pin "2") (pinfunction "2_2") (pintype "passive"))
    )
    (net (code "68") (name "unconnected-(JP8-Pad1)") (class "Default")
      (node (ref "JP8") (pin "1") (pinfunction "1_1") (pintype "passive"))
    )
    (net (code "69") (name "unconnected-(JP8-Pad2)") (class "Default")
      (node (ref "JP8") (pin "2") (pinfunction "2_2") (pintype "passive"))
    )
    (net (code "70") (name "unconnected-(JP9-Pad1)") (class "Default")
      (node (ref "JP9") (pin "1") (pinfunction "1_1") (pintype "passive"))
    )
    (net (code "71") (name "unconnected-(JP9-Pad2)") (class "Default")
      (node (ref "JP9") (pin "2") (pinfunction "2_2") (pintype "passive"))
    )
    (net (code "72") (name "unconnected-(JP10-Pad1)") (class "Default")
      (node (ref "JP10") (pin "1") (pinfunction "1_1") (pintype "passive"))
    )
    (net (code "73") (name "unconnected-(JP10-Pad2)") (class "Default")
      (node (ref "JP10") (pin "2") (pinfunction "2_2") (pintype "passive"))
    )
    (net (code "74") (name "unconnected-(JP11-Pad1)") (class "Default")
      (node (ref "JP11") (pin "1") (pinfunction "1_1") (pintype "passive"))
    )
    (net (code "75") (name "unconnected-(JP11-Pad2)") (class "Default")
      (node (ref "JP11") (pin "2") (pinfunction "2_2") (pintype "passive"))
    )
    (net (code "76") (name "unconnected-(JP13-Pad1)") (class "Default")
      (node (ref "JP13") (pin "1") (pinfunction "1_1") (pintype "passive"))
    )
    (net (code "77") (name "unconnected-(JP13-Pad2)") (class "Default")
      (node (ref "JP13") (pin "2") (pinfunction "2_2") (pintype "passive"))
    )
    (net (code "78") (name "unconnected-(JP15-Pad1)") (class "Default")
      (node (ref "JP15") (pin "1") (pinfunction "1_1") (pintype "passive"))
    )
    (net (code "79") (name "unconnected-(JP15-Pad2)") (class "Default")
      (node (ref "JP15") (pin "2") (pinfunction "2_2") (pintype "passive"))
    )
    (net (code "80") (name "unconnected-(JP15-Pad3)") (class "Default")
      (node (ref "JP15") (pin "3") (pinfunction "3_3") (pintype "passive"))
    )
    (net (code "81") (name "unconnected-(JP15-Pad4)") (class "Default")
      (node (ref "JP15") (pin "4") (pinfunction "4_4") (pintype "passive"))
    )
    (net (code "82") (name "unconnected-(JP15-Pad5)") (class "Default")
      (node (ref "JP15") (pin "5") (pinfunction "5_5") (pintype "passive"))
    )
    (net (code "83") (name "unconnected-(JP15-Pad6)") (class "Default")
      (node (ref "JP15") (pin "6") (pinfunction "6_6") (pintype "passive"))
    )
    (net (code "84") (name "unconnected-(JP15-Pad7)") (class "Default")
      (node (ref "JP15") (pin "7") (pinfunction "7_7") (pintype "passive"))
    )
    (net (code "85") (name "unconnected-(JP15-Pad8)") (class "Default")
      (node (ref "JP15") (pin "8") (pinfunction "8_8") (pintype "passive"))
    )
    (net (code "86") (name "unconnected-(JP15-Pad9)") (class "Default")
      (node (ref "JP15") (pin "9") (pinfunction "9_9") (pintype "passive"))
    )
    (net (code "87") (name "unconnected-(JP15-Pad10)") (class "Default")
      (node (ref "JP15") (pin "10") (pinfunction "10_10") (pintype "passive"))
    )
    (net (code "88") (name "unconnected-(JP15-Pad11)") (class "Default")
      (node (ref "JP15") (pin "11") (pinfunction "11_11") (pintype "passive"))
    )
    (net (code "89") (name "unconnected-(JP16-Pad1)") (class "Default")
      (node (ref "JP16") (pin "1") (pinfunction "1_1") (pintype "passive"))
    )
    (net (code "90") (name "unconnected-(JP16-Pad2)") (class "Default")
      (node (ref "JP16") (pin "2") (pinfunction "2_2") (pintype "passive"))
    )
    (net (code "91") (name "unconnected-(JP16-Pad3)") (class "Default")
      (node (ref "JP16") (pin "3") (pinfunction "3_3") (pintype "passive"))
    )
    (net (code "92") (name "unconnected-(JP16-Pad4)") (class "Default")
      (node (ref "JP16") (pin "4") (pinfunction "4_4") (pintype "passive"))
    )
    (net (code "93") (name "unconnected-(JP16-Pad5)") (class "Default")
      (node (ref "JP16") (pin "5") (pinfunction "5_5") (pintype "passive"))
    )
    (net (code "94") (name "unconnected-(JP16-Pad6)") (class "Default")
      (node (ref "JP16") (pin "6") (pinfunction "6_6") (pintype "passive"))
    )
    (net (code "95") (name "unconnected-(JP16-Pad7)") (class "Default")
      (node (ref "JP16") (pin "7") (pinfunction "7_7") (pintype "passive"))
    )
    (net (code "96") (name "unconnected-(JP16-Pad8)") (class "Default")
      (node (ref "JP16") (pin "8") (pinfunction "8_8") (pintype "passive"))
    )
    (net (code "97") (name "unconnected-(JP16-Pad9)") (class "Default")
      (node (ref "JP16") (pin "9") (pinfunction "9_9") (pintype "passive"))
    )
    (net (code "98") (name "unconnected-(JP16-Pad10)") (class "Default")
      (node (ref "JP16") (pin "10") (pinfunction "10_10") (pintype "passive"))
    )
    (net (code "99") (name "unconnected-(JP16-Pad11)") (class "Default")
      (node (ref "JP16") (pin "11") (pinfunction "11_11") (pintype "passive"))
    )
    (net (code "100") (name "unconnected-(JP17-Pad1)") (class "Default")
      (node (ref "JP17") (pin "1") (pinfunction "1_1") (pintype "passive"))
    )
    (net (code "101") (name "unconnected-(JP17-Pad2)") (class "Default")
      (node (ref "JP17") (pin "2") (pinfunction "2_2") (pintype "passive"))
    )
    (net (code "102") (name "unconnected-(JP17-Pad3)") (class "Default")
      (node (ref "JP17") (pin "3") (pinfunction "3_3") (pintype "passive"))
    )
    (net (code "103") (name "unconnected-(JP17-Pad4)") (class "Default")
      (node (ref "JP17") (pin "4") (pinfunction "4_4") (pintype "passive"))
    )
    (net (code "104") (name "unconnected-(JP17-Pad5)") (class "Default")
      (node (ref "JP17") (pin "5") (pinfunction "5_5") (pintype "passive"))
    )
    (net (code "105") (name "unconnected-(JP17-Pad6)") (class "Default")
      (node (ref "JP17") (pin "6") (pinfunction "6_6") (pintype "passive"))
    )
    (net (code "106") (name "unconnected-(JP17-Pad7)") (class "Default")
      (node (ref "JP17") (pin "7") (pinfunction "7_7") (pintype "passive"))
    )
    (net (code "107") (name "unconnected-(JP17-Pad8)") (class "Default")
      (node (ref "JP17") (pin "8") (pinfunction "8_8") (pintype "passive"))
    )
    (net (code "108") (name "unconnected-(JP17-Pad9)") (class "Default")
      (node (ref "JP17") (pin "9") (pinfunction "9_9") (pintype "passive"))
    )
    (net (code "109") (name "unconnected-(JP18-Pad1)") (class "Default")
      (node (ref "JP18") (pin "1") (pinfunction "1_1") (pintype "passive"))
    )
    (net (code "110") (name "unconnected-(JP18-Pad2)") (class "Default")
      (node (ref "JP18") (pin "2") (pinfunction "2_2") (pintype "passive"))
    )
    (net (code "111") (name "unconnected-(JP18-Pad3)") (class "Default")
      (node (ref "JP18") (pin "3") (pinfunction "3_3") (pintype "passive"))
    )
    (net (code "112") (name "unconnected-(JP18-Pad4)") (class "Default")
      (node (ref "JP18") (pin "4") (pinfunction "4_4") (pintype "passive"))
    )
    (net (code "113") (name "unconnected-(JP18-Pad5)") (class "Default")
      (node (ref "JP18") (pin "5") (pinfunction "5_5") (pintype "passive"))
    )
    (net (code "114") (name "unconnected-(JP18-Pad6)") (class "Default")
      (node (ref "JP18") (pin "6") (pinfunction "6_6") (pintype "passive"))
    )
    (net (code "115") (name "unconnected-(JP18-Pad7)") (class "Default")
      (node (ref "JP18") (pin "7") (pinfunction "7_7") (pintype "passive"))
    )
    (net (code "116") (name "unconnected-(JP18-Pad8)") (class "Default")
      (node (ref "JP18") (pin "8") (pinfunction "8_8") (pintype "passive"))
    )
    (net (code "117") (name "unconnected-(JP18-Pad9)") (class "Default")
      (node (ref "JP18") (pin "9") (pinfunction "9_9") (pintype "passive"))
    )
    (net (code "118") (name "unconnected-(JP19-Pad1)") (class "Default")
      (node (ref "JP19") (pin "1") (pinfunction "1_1") (pintype "passive"))
    )
    (net (code "119") (name "unconnected-(JP19-Pad2)") (class "Default")
      (node (ref "JP19") (pin "2") (pinfunction "2_2") (pintype "passive"))
    )
    (net (code "120") (name "unconnected-(JP20-Pad1)") (class "Default")
      (node (ref "JP20") (pin "1") (pinfunction "1_1") (pintype "passive"))
    )
    (net (code "121") (name "unconnected-(JP20-Pad2)") (class "Default")
      (node (ref "JP20") (pin "2") (pinfunction "2_2") (pintype "passive"))
    )
    (net (code "122") (name "unconnected-(JP21-Pad1)") (class "Default")
      (node (ref "JP21") (pin "1") (pinfunction "1_1") (pintype "passive"))
    )
    (net (code "123") (name "unconnected-(JP21-Pad2)") (class "Default")
      (node (ref "JP21") (pin "2") (pinfunction "2_2") (pintype "passive"))
    )
    (net (code "124") (name "unconnected-(JP21-Pad3)") (class "Default")
      (node (ref "JP21") (pin "3") (pinfunction "3_3") (pintype "passive"))
    )
    (net (code "125") (name "unconnected-(JP21-Pad4)") (class "Default")
      (node (ref "JP21") (pin "4") (pinfunction "4_4") (pintype "passive"))
    )
    (net (code "126") (name "unconnected-(JP21-Pad5)") (class "Default")
      (node (ref "JP21") (pin "5") (pinfunction "5_5") (pintype "passive"))
    )
    (net (code "127") (name "unconnected-(JP21-Pad6)") (class "Default")
      (node (ref "JP21") (pin "6") (pinfunction "6_6") (pintype "passive"))
    )
    (net (code "128") (name "unconnected-(JP21-Pad7)") (class "Default")
      (node (ref "JP21") (pin "7") (pinfunction "7_7") (pintype "passive"))
    )
    (net (code "129") (name "unconnected-(JP21-Pad8)") (class "Default")
      (node (ref "JP21") (pin "8") (pinfunction "8_8") (pintype "passive"))
    )
    (net (code "130") (name "unconnected-(JP21-Pad9)") (class "Default")
      (node (ref "JP21") (pin "9") (pinfunction "9_9") (pintype "passive"))
    )
    (net (code "131") (name "unconnected-(JP21-Pad10)") (class "Default")
      (node (ref "JP21") (pin "10") (pinfunction "10_10") (pintype "passive"))
    )
    (net (code "132") (name "unconnected-(JP23-Pad1)") (class "Default")
      (node (ref "JP23") (pin "1") (pinfunction "1_1") (pintype "passive"))
    )
    (net (code "133") (name "unconnected-(JP23-Pad2)") (class "Default")
      (node (ref "JP23") (pin "2") (pinfunction "2_2") (pintype "passive"))
    )
    (net (code "134") (name "unconnected-(JP23-Pad3)") (class "Default")
      (node (ref "JP23") (pin "3") (pinfunction "3_3") (pintype "passive"))
    )
    (net (code "135") (name "unconnected-(JP23-Pad4)") (class "Default")
      (node (ref "JP23") (pin "4") (pinfunction "4_4") (pintype "passive"))
    )
    (net (code "136") (name "unconnected-(JP23-Pad5)") (class "Default")
      (node (ref "JP23") (pin "5") (pinfunction "5_5") (pintype "passive"))
    )
    (net (code "137") (name "unconnected-(JP23-Pad6)") (class "Default")
      (node (ref "JP23") (pin "6") (pinfunction "6_6") (pintype "passive"))
    )
    (net (code "138") (name "unconnected-(JP23-Pad7)") (class "Default")
      (node (ref "JP23") (pin "7") (pinfunction "7_7") (pintype "passive"))
    )
    (net (code "139") (name "unconnected-(JP23-Pad8)") (class "Default")
      (node (ref "JP23") (pin "8") (pinfunction "8_8") (pintype "passive"))
    )
    (net (code "140") (name "unconnected-(JP23-Pad9)") (class "Default")
      (node (ref "JP23") (pin "9") (pinfunction "9_9") (pintype "passive"))
    )
    (net (code "141") (name "unconnected-(JP23-Pad10)") (class "Default")
      (node (ref "JP23") (pin "10") (pinfunction "10_10") (pintype "passive"))
    )
    (net (code "142") (name "unconnected-(JP23-Pad11)") (class "Default")
      (node (ref "JP23") (pin "11") (pinfunction "11_11") (pintype "passive"))
    )
    (net (code "143") (name "unconnected-(JP25-Pad1)") (class "Default")
      (node (ref "JP25") (pin "1") (pinfunction "1_1") (pintype "passive"))
    )
    (net (code "144") (name "unconnected-(JP25-Pad2)") (class "Default")
      (node (ref "JP25") (pin "2") (pinfunction "2_2") (pintype "passive"))
    )
    (net (code "145") (name "unconnected-(JP25-Pad3)") (class "Default")
      (node (ref "JP25") (pin "3") (pinfunction "3_3") (pintype "passive"))
    )
    (net (code "146") (name "unconnected-(JP25-Pad4)") (class "Default")
      (node (ref "JP25") (pin "4") (pinfunction "4_4") (pintype "passive"))
    )
    (net (code "147") (name "unconnected-(JP25-Pad5)") (class "Default")
      (node (ref "JP25") (pin "5") (pinfunction "5_5") (pintype "passive"))
    )
    (net (code "148") (name "unconnected-(JP25-Pad6)") (class "Default")
      (node (ref "JP25") (pin "6") (pinfunction "6_6") (pintype "passive"))
    )
    (net (code "149") (name "unconnected-(JP25-Pad7)") (class "Default")
      (node (ref "JP25") (pin "7") (pinfunction "7_7") (pintype "passive"))
    )
    (net (code "150") (name "unconnected-(JP25-Pad8)") (class "Default")
      (node (ref "JP25") (pin "8") (pinfunction "8_8") (pintype "passive"))
    )
    (net (code "151") (name "unconnected-(JP25-Pad9)") (class "Default")
      (node (ref "JP25") (pin "9") (pinfunction "9_9") (pintype "passive"))
    )
    (net (code "152") (name "unconnected-(JP25-Pad10)") (class "Default")
      (node (ref "JP25") (pin "10") (pinfunction "10_10") (pintype "passive"))
    )
    (net (code "153") (name "unconnected-(JP25-Pad11)") (class "Default")
      (node (ref "JP25") (pin "11") (pinfunction "11_11") (pintype "passive"))
    )
    (net (code "154") (name "unconnected-(JP26-Pad1)") (class "Default")
      (node (ref "JP26") (pin "1") (pinfunction "1_1") (pintype "passive"))
    )
    (net (code "155") (name "unconnected-(JP26-Pad2)") (class "Default")
      (node (ref "JP26") (pin "2") (pinfunction "2_2") (pintype "passive"))
    )
    (net (code "156") (name "unconnected-(JP26-Pad3)") (class "Default")
      (node (ref "JP26") (pin "3") (pinfunction "3_3") (pintype "passive"))
    )
    (net (code "157") (name "unconnected-(JP26-Pad4)") (class "Default")
      (node (ref "JP26") (pin "4") (pinfunction "4_4") (pintype "passive"))
    )
    (net (code "158") (name "unconnected-(JP26-Pad5)") (class "Default")
      (node (ref "JP26") (pin "5") (pinfunction "5_5") (pintype "passive"))
    )
    (net (code "159") (name "unconnected-(JP26-Pad6)") (class "Default")
      (node (ref "JP26") (pin "6") (pinfunction "6_6") (pintype "passive"))
    )
    (net (code "160") (name "unconnected-(JP26-Pad7)") (class "Default")
      (node (ref "JP26") (pin "7") (pinfunction "7_7") (pintype "passive"))
    )
    (net (code "161") (name "unconnected-(JP26-Pad8)") (class "Default")
      (node (ref "JP26") (pin "8") (pinfunction "8_8") (pintype "passive"))
    )
    (net (code "162") (name "unconnected-(JP26-Pad9)") (class "Default")
      (node (ref "JP26") (pin "9") (pinfunction "9_9") (pintype "passive"))
    )
    (net (code "163") (name "unconnected-(JP26-Pad10)") (class "Default")
      (node (ref "JP26") (pin "10") (pinfunction "10_10") (pintype "passive"))
    )
    (net (code "164") (name "unconnected-(JP26-Pad11)") (class "Default")
      (node (ref "JP26") (pin "11") (pinfunction "11_11") (pintype "passive"))
    )
    (net (code "165") (name "unconnected-(JP27-Pad1)") (class "Default")
      (node (ref "JP27") (pin "1") (pinfunction "1_1") (pintype "passive"))
    )
    (net (code "166") (name "unconnected-(JP27-Pad2)") (class "Default")
      (node (ref "JP27") (pin "2") (pinfunction "2_2") (pintype "passive"))
    )
    (net (code "167") (name "unconnected-(JP27-Pad3)") (class "Default")
      (node (ref "JP27") (pin "3") (pinfunction "3_3") (pintype "passive"))
    )
    (net (code "168") (name "unconnected-(JP27-Pad4)") (class "Default")
      (node (ref "JP27") (pin "4") (pinfunction "4_4") (pintype "passive"))
    )
    (net (code "169") (name "unconnected-(JP27-Pad5)") (class "Default")
      (node (ref "JP27") (pin "5") (pinfunction "5_5") (pintype "passive"))
    )
    (net (code "170") (name "unconnected-(JP27-Pad6)") (class "Default")
      (node (ref "JP27") (pin "6") (pinfunction "6_6") (pintype "passive"))
    )
    (net (code "171") (name "unconnected-(JP27-Pad7)") (class "Default")
      (node (ref "JP27") (pin "7") (pinfunction "7_7") (pintype "passive"))
    )
    (net (code "172") (name "unconnected-(JP27-Pad8)") (class "Default")
      (node (ref "JP27") (pin "8") (pinfunction "8_8") (pintype "passive"))
    )
    (net (code "173") (name "unconnected-(JP27-Pad9)") (class "Default")
      (node (ref "JP27") (pin "9") (pinfunction "9_9") (pintype "passive"))
    )
    (net (code "174") (name "unconnected-(JP27-Pad10)") (class "Default")
      (node (ref "JP27") (pin "10") (pinfunction "10_10") (pintype "passive"))
    )
    (net (code "175") (name "unconnected-(JP27-Pad11)") (class "Default")
      (node (ref "JP27") (pin "11") (pinfunction "11_11") (pintype "passive"))
    )
    (net (code "176") (name "unconnected-(JP28-Pad1)") (class "Default")
      (node (ref "JP28") (pin "1") (pinfunction "1_1") (pintype "passive"))
    )
    (net (code "177") (name "unconnected-(JP28-Pad2)") (class "Default")
      (node (ref "JP28") (pin "2") (pinfunction "2_2") (pintype "passive"))
    )
    (net (code "178") (name "unconnected-(JP28-Pad3)") (class "Default")
      (node (ref "JP28") (pin "3") (pinfunction "3_3") (pintype "passive"))
    )
    (net (code "179") (name "unconnected-(JP28-Pad4)") (class "Default")
      (node (ref "JP28") (pin "4") (pinfunction "4_4") (pintype "passive"))
    )
    (net (code "180") (name "unconnected-(JP28-Pad5)") (class "Default")
      (node (ref "JP28") (pin "5") (pinfunction "5_5") (pintype "passive"))
    )
    (net (code "181") (name "unconnected-(JP28-Pad6)") (class "Default")
      (node (ref "JP28") (pin "6") (pinfunction "6_6") (pintype "passive"))
    )
    (net (code "182") (name "unconnected-(JP28-Pad7)") (class "Default")
      (node (ref "JP28") (pin "7") (pinfunction "7_7") (pintype "passive"))
    )
    (net (code "183") (name "unconnected-(JP28-Pad8)") (class "Default")
      (node (ref "JP28") (pin "8") (pinfunction "8_8") (pintype "passive"))
    )
    (net (code "184") (name "unconnected-(JP28-Pad9)") (class "Default")
      (node (ref "JP28") (pin "9") (pinfunction "9_9") (pintype "passive"))
    )
    (net (code "185") (name "unconnected-(JP28-Pad10)") (class "Default")
      (node (ref "JP28") (pin "10") (pinfunction "10_10") (pintype "passive"))
    )
    (net (code "186") (name "unconnected-(JP28-Pad11)") (class "Default")
      (node (ref "JP28") (pin "11") (pinfunction "11_11") (pintype "passive"))
    )
    (net (code "187") (name "unconnected-(JP29-Pad1)") (class "Default")
      (node (ref "JP29") (pin "1") (pinfunction "1_1") (pintype "passive"))
    )
    (net (code "188") (name "unconnected-(JP29-Pad2)") (class "Default")
      (node (ref "JP29") (pin "2") (pinfunction "2_2") (pintype "passive"))
    )
    (net (code "189") (name "unconnected-(JP29-Pad3)") (class "Default")
      (node (ref "JP29") (pin "3") (pinfunction "3_3") (pintype "passive"))
    )
    (net (code "190") (name "unconnected-(JP29-Pad4)") (class "Default")
      (node (ref "JP29") (pin "4") (pinfunction "4_4") (pintype "passive"))
    )
    (net (code "191") (name "unconnected-(JP29-Pad5)") (class "Default")
      (node (ref "JP29") (pin "5") (pinfunction "5_5") (pintype "passive"))
    )
    (net (code "192") (name "unconnected-(JP29-Pad6)") (class "Default")
      (node (ref "JP29") (pin "6") (pinfunction "6_6") (pintype "passive"))
    )
    (net (code "193") (name "unconnected-(JP29-Pad7)") (class "Default")
      (node (ref "JP29") (pin "7") (pinfunction "7_7") (pintype "passive"))
    )
    (net (code "194") (name "unconnected-(JP29-Pad8)") (class "Default")
      (node (ref "JP29") (pin "8") (pinfunction "8_8") (pintype "passive"))
    )
    (net (code "195") (name "unconnected-(JP29-Pad9)") (class "Default")
      (node (ref "JP29") (pin "9") (pinfunction "9_9") (pintype "passive"))
    )
    (net (code "196") (name "unconnected-(JP29-Pad10)") (class "Default")
      (node (ref "JP29") (pin "10") (pinfunction "10_10") (pintype "passive"))
    )
    (net (code "197") (name "unconnected-(JP29-Pad11)") (class "Default")
      (node (ref "JP29") (pin "11") (pinfunction "11_11") (pintype "passive"))
    )
    (net (code "198") (name "unconnected-(JP30-Pad1)") (class "Default")
      (node (ref "JP30") (pin "1") (pinfunction "1_1") (pintype "passive"))
    )
    (net (code "199") (name "unconnected-(JP30-Pad2)") (class "Default")
      (node (ref "JP30") (pin "2") (pinfunction "2_2") (pintype "passive"))
    )
    (net (code "200") (name "unconnected-(JP30-Pad3)") (class "Default")
      (node (ref "JP30") (pin "3") (pinfunction "3_3") (pintype "passive"))
    )
    (net (code "201") (name "unconnected-(JP30-Pad4)") (class "Default")
      (node (ref "JP30") (pin "4") (pinfunction "4_4") (pintype "passive"))
    )
    (net (code "202") (name "unconnected-(JP30-Pad5)") (class "Default")
      (node (ref "JP30") (pin "5") (pinfunction "5_5") (pintype "passive"))
    )
    (net (code "203") (name "unconnected-(JP30-Pad6)") (class "Default")
      (node (ref "JP30") (pin "6") (pinfunction "6_6") (pintype "passive"))
    )
    (net (code "204") (name "unconnected-(JP30-Pad7)") (class "Default")
      (node (ref "JP30") (pin "7") (pinfunction "7_7") (pintype "passive"))
    )
    (net (code "205") (name "unconnected-(JP30-Pad8)") (class "Default")
      (node (ref "JP30") (pin "8") (pinfunction "8_8") (pintype "passive"))
    )
    (net (code "206") (name "unconnected-(JP30-Pad9)") (class "Default")
      (node (ref "JP30") (pin "9") (pinfunction "9_9") (pintype "passive"))
    )
    (net (code "207") (name "unconnected-(JP30-Pad10)") (class "Default")
      (node (ref "JP30") (pin "10") (pinfunction "10_10") (pintype "passive"))
    )
    (net (code "208") (name "unconnected-(JP31-Pad1)") (class "Default")
      (node (ref "JP31") (pin "1") (pinfunction "1_1") (pintype "passive"))
    )
    (net (code "209") (name "unconnected-(JP31-Pad2)") (class "Default")
      (node (ref "JP31") (pin "2") (pinfunction "2_2") (pintype "passive"))
    )
    (net (code "210") (name "unconnected-(JP31-Pad3)") (class "Default")
      (node (ref "JP31") (pin "3") (pinfunction "3_3") (pintype "passive"))
    )
    (net (code "211") (name "unconnected-(JP31-Pad4)") (class "Default")
      (node (ref "JP31") (pin "4") (pinfunction "4_4") (pintype "passive"))
    )
    (net (code "212") (name "unconnected-(JP31-Pad5)") (class "Default")
      (node (ref "JP31") (pin "5") (pinfunction "5_5") (pintype "passive"))
    )
    (net (code "213") (name "unconnected-(JP31-Pad6)") (class "Default")
      (node (ref "JP31") (pin "6") (pinfunction "6_6") (pintype "passive"))
    )
    (net (code "214") (name "unconnected-(JP31-Pad7)") (class "Default")
      (node (ref "JP31") (pin "7") (pinfunction "7_7") (pintype "passive"))
    )
    (net (code "215") (name "unconnected-(JP31-Pad8)") (class "Default")
      (node (ref "JP31") (pin "8") (pinfunction "8_8") (pintype "passive"))
    )
    (net (code "216") (name "unconnected-(JP31-Pad9)") (class "Default")
      (node (ref "JP31") (pin "9") (pinfunction "9_9") (pintype "passive"))
    )
    (net (code "217") (name "unconnected-(JP32-Pad1)") (class "Default")
      (node (ref "JP32") (pin "1") (pinfunction "1_1") (pintype "passive"))
    )
    (net (code "218") (name "unconnected-(JP32-Pad2)") (class "Default")
      (node (ref "JP32") (pin "2") (pinfunction "2_2") (pintype "passive"))
    )
    (net (code "219") (name "unconnected-(JP32-Pad3)") (class "Default")
      (node (ref "JP32") (pin "3") (pinfunction "3_3") (pintype "passive"))
    )
    (net (code "220") (name "unconnected-(JP32-Pad4)") (class "Default")
      (node (ref "JP32") (pin "4") (pinfunction "4_4") (pintype "passive"))
    )
    (net (code "221") (name "unconnected-(JP32-Pad5)") (class "Default")
      (node (ref "JP32") (pin "5") (pinfunction "5_5") (pintype "passive"))
    )
    (net (code "222") (name "unconnected-(JP32-Pad6)") (class "Default")
      (node (ref "JP32") (pin "6") (pinfunction "6_6") (pintype "passive"))
    )
    (net (code "223") (name "unconnected-(JP32-Pad7)") (class "Default")
      (node (ref "JP32") (pin "7") (pinfunction "7_7") (pintype "passive"))
    )
    (net (code "224") (name "unconnected-(JP32-Pad8)") (class "Default")
      (node (ref "JP32") (pin "8") (pinfunction "8_8") (pintype "passive"))
    )
    (net (code "225") (name "unconnected-(JP32-Pad9)") (class "Default")
      (node (ref "JP32") (pin "9") (pinfunction "9_9") (pintype "passive"))
    )
    (net (code "226") (name "unconnected-(JP32-Pad10)") (class "Default")
      (node (ref "JP32") (pin "10") (pinfunction "10_10") (pintype "passive"))
    )
    (net (code "227") (name "unconnected-(JP32-Pad11)") (class "Default")
      (node (ref "JP32") (pin "11") (pinfunction "11_11") (pintype "passive"))
    )
    (net (code "228") (name "unconnected-(JP33-Pad1)") (class "Default")
      (node (ref "JP33") (pin "1") (pinfunction "1_1") (pintype "passive"))
    )
    (net (code "229") (name "unconnected-(JP33-Pad2)") (class "Default")
      (node (ref "JP33") (pin "2") (pinfunction "2_2") (pintype "passive"))
    )
    (net (code "230") (name "unconnected-(JP33-Pad3)") (class "Default")
      (node (ref "JP33") (pin "3") (pinfunction "3_3") (pintype "passive"))
    )
    (net (code "231") (name "unconnected-(JP33-Pad4)") (class "Default")
      (node (ref "JP33") (pin "4") (pinfunction "4_4") (pintype "passive"))
    )
    (net (code "232") (name "unconnected-(JP33-Pad5)") (class "Default")
      (node (ref "JP33") (pin "5") (pinfunction "5_5") (pintype "passive"))
    )
    (net (code "233") (name "unconnected-(JP33-Pad6)") (class "Default")
      (node (ref "JP33") (pin "6") (pinfunction "6_6") (pintype "passive"))
    )
    (net (code "234") (name "unconnected-(JP33-Pad7)") (class "Default")
      (node (ref "JP33") (pin "7") (pinfunction "7_7") (pintype "passive"))
    )
    (net (code "235") (name "unconnected-(JP33-Pad8)") (class "Default")
      (node (ref "JP33") (pin "8") (pinfunction "8_8") (pintype "passive"))
    )
    (net (code "236") (name "unconnected-(JP33-Pad9)") (class "Default")
      (node (ref "JP33") (pin "9") (pinfunction "9_9") (pintype "passive"))
    )
    (net (code "237") (name "unconnected-(JP34-Pad1)") (class "Default")
      (node (ref "JP34") (pin "1") (pinfunction "1_1") (pintype "passive"))
    )
    (net (code "238") (name "unconnected-(JP34-Pad2)") (class "Default")
      (node (ref "JP34") (pin "2") (pinfunction "2_2") (pintype "passive"))
    )
    (net (code "239") (name "unconnected-(JP34-Pad3)") (class "Default")
      (node (ref "JP34") (pin "3") (pinfunction "3_3") (pintype "passive"))
    )
    (net (code "240") (name "unconnected-(JP34-Pad4)") (class "Default")
      (node (ref "JP34") (pin "4") (pinfunction "4_4") (pintype "passive"))
    )
    (net (code "241") (name "unconnected-(JP34-Pad5)") (class "Default")
      (node (ref "JP34") (pin "5") (pinfunction "5_5") (pintype "passive"))
    )
    (net (code "242") (name "unconnected-(JP34-Pad6)") (class "Default")
      (node (ref "JP34") (pin "6") (pinfunction "6_6") (pintype "passive"))
    )
    (net (code "243") (name "unconnected-(JP34-Pad7)") (class "Default")
      (node (ref "JP34") (pin "7") (pinfunction "7_7") (pintype "passive"))
    )
    (net (code "244") (name "unconnected-(JP34-Pad8)") (class "Default")
      (node (ref "JP34") (pin "8") (pinfunction "8_8") (pintype "passive"))
    )
    (net (code "245") (name "unconnected-(JP34-Pad9)") (class "Default")
      (node (ref "JP34") (pin "9") (pinfunction "9_9") (pintype "passive"))
    )
    (net (code "246") (name "unconnected-(JP34-Pad10)") (class "Default")
      (node (ref "JP34") (pin "10") (pinfunction "10_10") (pintype "passive"))
    )
    (net (code "247") (name "unconnected-(JP34-Pad11)") (class "Default")
      (node (ref "JP34") (pin "11") (pinfunction "11_11") (pintype "passive"))
    )
    (net (code "248") (name "unconnected-(JP35-Pad1)") (class "Default")
      (node (ref "JP35") (pin "1") (pinfunction "1_1") (pintype "passive"))
    )
    (net (code "249") (name "unconnected-(JP35-Pad2)") (class "Default")
      (node (ref "JP35") (pin "2") (pinfunction "2_2") (pintype "passive"))
    )
    (net (code "250") (name "unconnected-(JP35-Pad3)") (class "Default")
      (node (ref "JP35") (pin "3") (pinfunction "3_3") (pintype "passive"))
    )
    (net (code "251") (name "unconnected-(JP35-Pad4)") (class "Default")
      (node (ref "JP35") (pin "4") (pinfunction "4_4") (pintype "passive"))
    )
    (net (code "252") (name "unconnected-(JP35-Pad5)") (class "Default")
      (node (ref "JP35") (pin "5") (pinfunction "5_5") (pintype "passive"))
    )
    (net (code "253") (name "unconnected-(JP35-Pad6)") (class "Default")
      (node (ref "JP35") (pin "6") (pinfunction "6_6") (pintype "passive"))
    )
    (net (code "254") (name "unconnected-(JP35-Pad7)") (class "Default")
      (node (ref "JP35") (pin "7") (pinfunction "7_7") (pintype "passive"))
    )
    (net (code "255") (name "unconnected-(JP35-Pad8)") (class "Default")
      (node (ref "JP35") (pin "8") (pinfunction "8_8") (pintype "passive"))
    )
    (net (code "256") (name "unconnected-(JP35-Pad9)") (class "Default")
      (node (ref "JP35") (pin "9") (pinfunction "9_9") (pintype "passive"))
    )
    (net (code "257") (name "unconnected-(JP35-Pad10)") (class "Default")
      (node (ref "JP35") (pin "10") (pinfunction "10_10") (pintype "passive"))
    )
    (net (code "258") (name "unconnected-(JP36-Pad1)") (class "Default")
      (node (ref "JP36") (pin "1") (pinfunction "1_1") (pintype "passive"))
    )
    (net (code "259") (name "unconnected-(JP36-Pad2)") (class "Default")
      (node (ref "JP36") (pin "2") (pinfunction "2_2") (pintype "passive"))
    )
    (net (code "260") (name "unconnected-(JP36-Pad3)") (class "Default")
      (node (ref "JP36") (pin "3") (pinfunction "3_3") (pintype "passive"))
    )
    (net (code "261") (name "unconnected-(JP36-Pad4)") (class "Default")
      (node (ref "JP36") (pin "4") (pinfunction "4_4") (pintype "passive"))
    )
    (net (code "262") (name "unconnected-(JP36-Pad5)") (class "Default")
      (node (ref "JP36") (pin "5") (pinfunction "5_5") (pintype "passive"))
    )
    (net (code "263") (name "unconnected-(JP36-Pad6)") (class "Default")
      (node (ref "JP36") (pin "6") (pinfunction "6_6") (pintype "passive"))
    )
    (net (code "264") (name "unconnected-(JP36-Pad7)") (class "Default")
      (node (ref "JP36") (pin "7") (pinfunction "7_7") (pintype "passive"))
    )
    (net (code "265") (name "unconnected-(JP36-Pad8)") (class "Default")
      (node (ref "JP36") (pin "8") (pinfunction "8_8") (pintype "passive"))
    )
    (net (code "266") (name "unconnected-(JP37-Pad1)") (class "Default")
      (node (ref "JP37") (pin "1") (pinfunction "1_1") (pintype "passive"))
    )
    (net (code "267") (name "unconnected-(JP37-Pad2)") (class "Default")
      (node (ref "JP37") (pin "2") (pinfunction "2_2") (pintype "passive"))
    )
    (net (code "268") (name "unconnected-(JP37-Pad3)") (class "Default")
      (node (ref "JP37") (pin "3") (pinfunction "3_3") (pintype "passive"))
    )
    (net (code "269") (name "unconnected-(JP37-Pad4)") (class "Default")
      (node (ref "JP37") (pin "4") (pinfunction "4_4") (pintype "passive"))
    )
    (net (code "270") (name "unconnected-(JP37-Pad5)") (class "Default")
      (node (ref "JP37") (pin "5") (pinfunction "5_5") (pintype "passive"))
    )
    (net (code "271") (name "unconnected-(JP37-Pad6)") (class "Default")
      (node (ref "JP37") (pin "6") (pinfunction "6_6") (pintype "passive"))
    )
    (net (code "272") (name "unconnected-(JP37-Pad7)") (class "Default")
      (node (ref "JP37") (pin "7") (pinfunction "7_7") (pintype "passive"))
    )
    (net (code "273") (name "unconnected-(JP37-Pad8)") (class "Default")
      (node (ref "JP37") (pin "8") (pinfunction "8_8") (pintype "passive"))
    )
    (net (code "274") (name "unconnected-(JP38-Pad1)") (class "Default")
      (node (ref "JP38") (pin "1") (pinfunction "1_1") (pintype "passive"))
    )
    (net (code "275") (name "unconnected-(JP38-Pad2)") (class "Default")
      (node (ref "JP38") (pin "2") (pinfunction "2_2") (pintype "passive"))
    )
    (net (code "276") (name "unconnected-(JP38-Pad3)") (class "Default")
      (node (ref "JP38") (pin "3") (pinfunction "3_3") (pintype "passive"))
    )
    (net (code "277") (name "unconnected-(JP38-Pad4)") (class "Default")
      (node (ref "JP38") (pin "4") (pinfunction "4_4") (pintype "passive"))
    )
    (net (code "278") (name "unconnected-(JP38-Pad5)") (class "Default")
      (node (ref "JP38") (pin "5") (pinfunction "5_5") (pintype "passive"))
    )
    (net (code "279") (name "unconnected-(JP38-Pad6)") (class "Default")
      (node (ref "JP38") (pin "6") (pinfunction "6_6") (pintype "passive"))
    )
    (net (code "280") (name "unconnected-(JP38-Pad7)") (class "Default")
      (node (ref "JP38") (pin "7") (pinfunction "7_7") (pintype "passive"))
    )
    (net (code "281") (name "unconnected-(JP38-Pad8)") (class "Default")
      (node (ref "JP38") (pin "8") (pinfunction "8_8") (pintype "passive"))
    )
    (net (code "282") (name "unconnected-(JP39-Pad1)") (class "Default")
      (node (ref "JP39") (pin "1") (pinfunction "1_1") (pintype "passive"))
    )
    (net (code "283") (name "unconnected-(JP39-Pad2)") (class "Default")
      (node (ref "JP39") (pin "2") (pinfunction "2_2") (pintype "passive"))
    )
    (net (code "284") (name "unconnected-(JP39-Pad3)") (class "Default")
      (node (ref "JP39") (pin "3") (pinfunction "3_3") (pintype "passive"))
    )
    (net (code "285") (name "unconnected-(JP39-Pad4)") (class "Default")
      (node (ref "JP39") (pin "4") (pinfunction "4_4") (pintype "passive"))
    )
    (net (code "286") (name "unconnected-(JP39-Pad5)") (class "Default")
      (node (ref "JP39") (pin "5") (pinfunction "5_5") (pintype "passive"))
    )
    (net (code "287") (name "unconnected-(JP39-Pad6)") (class "Default")
      (node (ref "JP39") (pin "6") (pinfunction "6_6") (pintype "passive"))
    )
    (net (code "288") (name "unconnected-(JP39-Pad7)") (class "Default")
      (node (ref "JP39") (pin "7") (pinfunction "7_7") (pintype "passive"))
    )
    (net (code "289") (name "unconnected-(JP39-Pad8)") (class "Default")
      (node (ref "JP39") (pin "8") (pinfunction "8_8") (pintype "passive"))
    )
    (net (code "290") (name "unconnected-(JP43-Pad1)") (class "Default")
      (node (ref "JP43") (pin "1") (pinfunction "1_1") (pintype "passive"))
    )
    (net (code "291") (name "unconnected-(JP43-Pad2)") (class "Default")
      (node (ref "JP43") (pin "2") (pinfunction "2_2") (pintype "passive"))
    )
    (net (code "292") (name "unconnected-(JP44-Pad1)") (class "Default")
      (node (ref "JP44") (pin "1") (pinfunction "1_1") (pintype "passive"))
    )
    (net (code "293") (name "unconnected-(JP44-Pad2)") (class "Default")
      (node (ref "JP44") (pin "2") (pinfunction "2_2") (pintype "passive"))
    )
    (net (code "294") (name "unconnected-(JP60-Pad1)") (class "Default")
      (node (ref "JP60") (pin "1") (pinfunction "1_1") (pintype "passive"))
    )
    (net (code "295") (name "unconnected-(JP60-Pad2)") (class "Default")
      (node (ref "JP60") (pin "2") (pinfunction "2_2") (pintype "passive"))
    )
  )
)
